# S7G7_footprint_simplified_w_ethernet_v1p.net
KiCad netlist of a schematic drawn in EAGLE
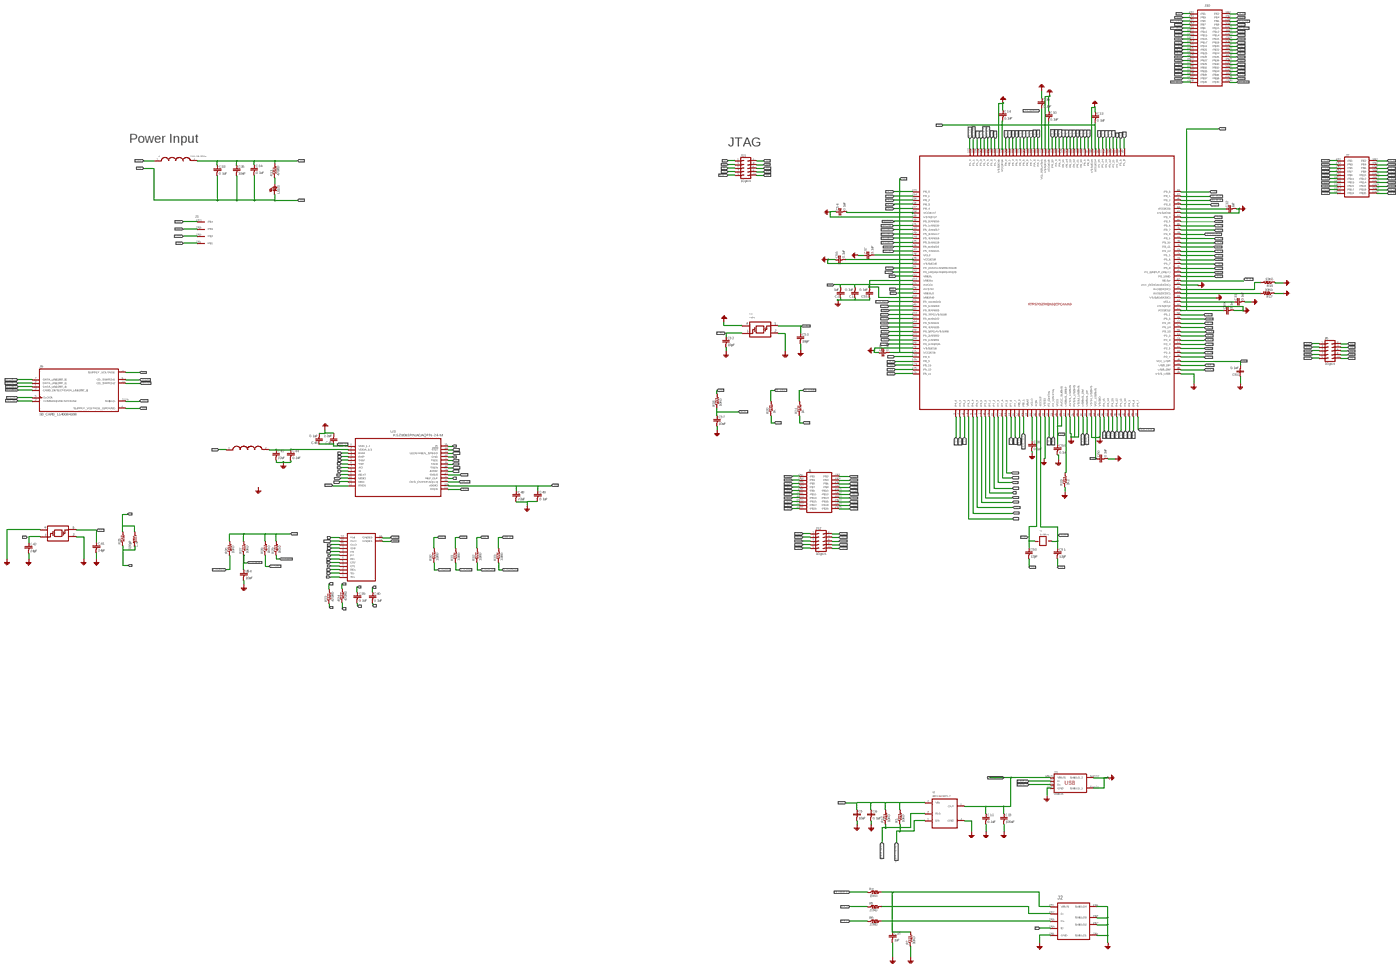
[diagram p0: schematic, sheet 1, overview]
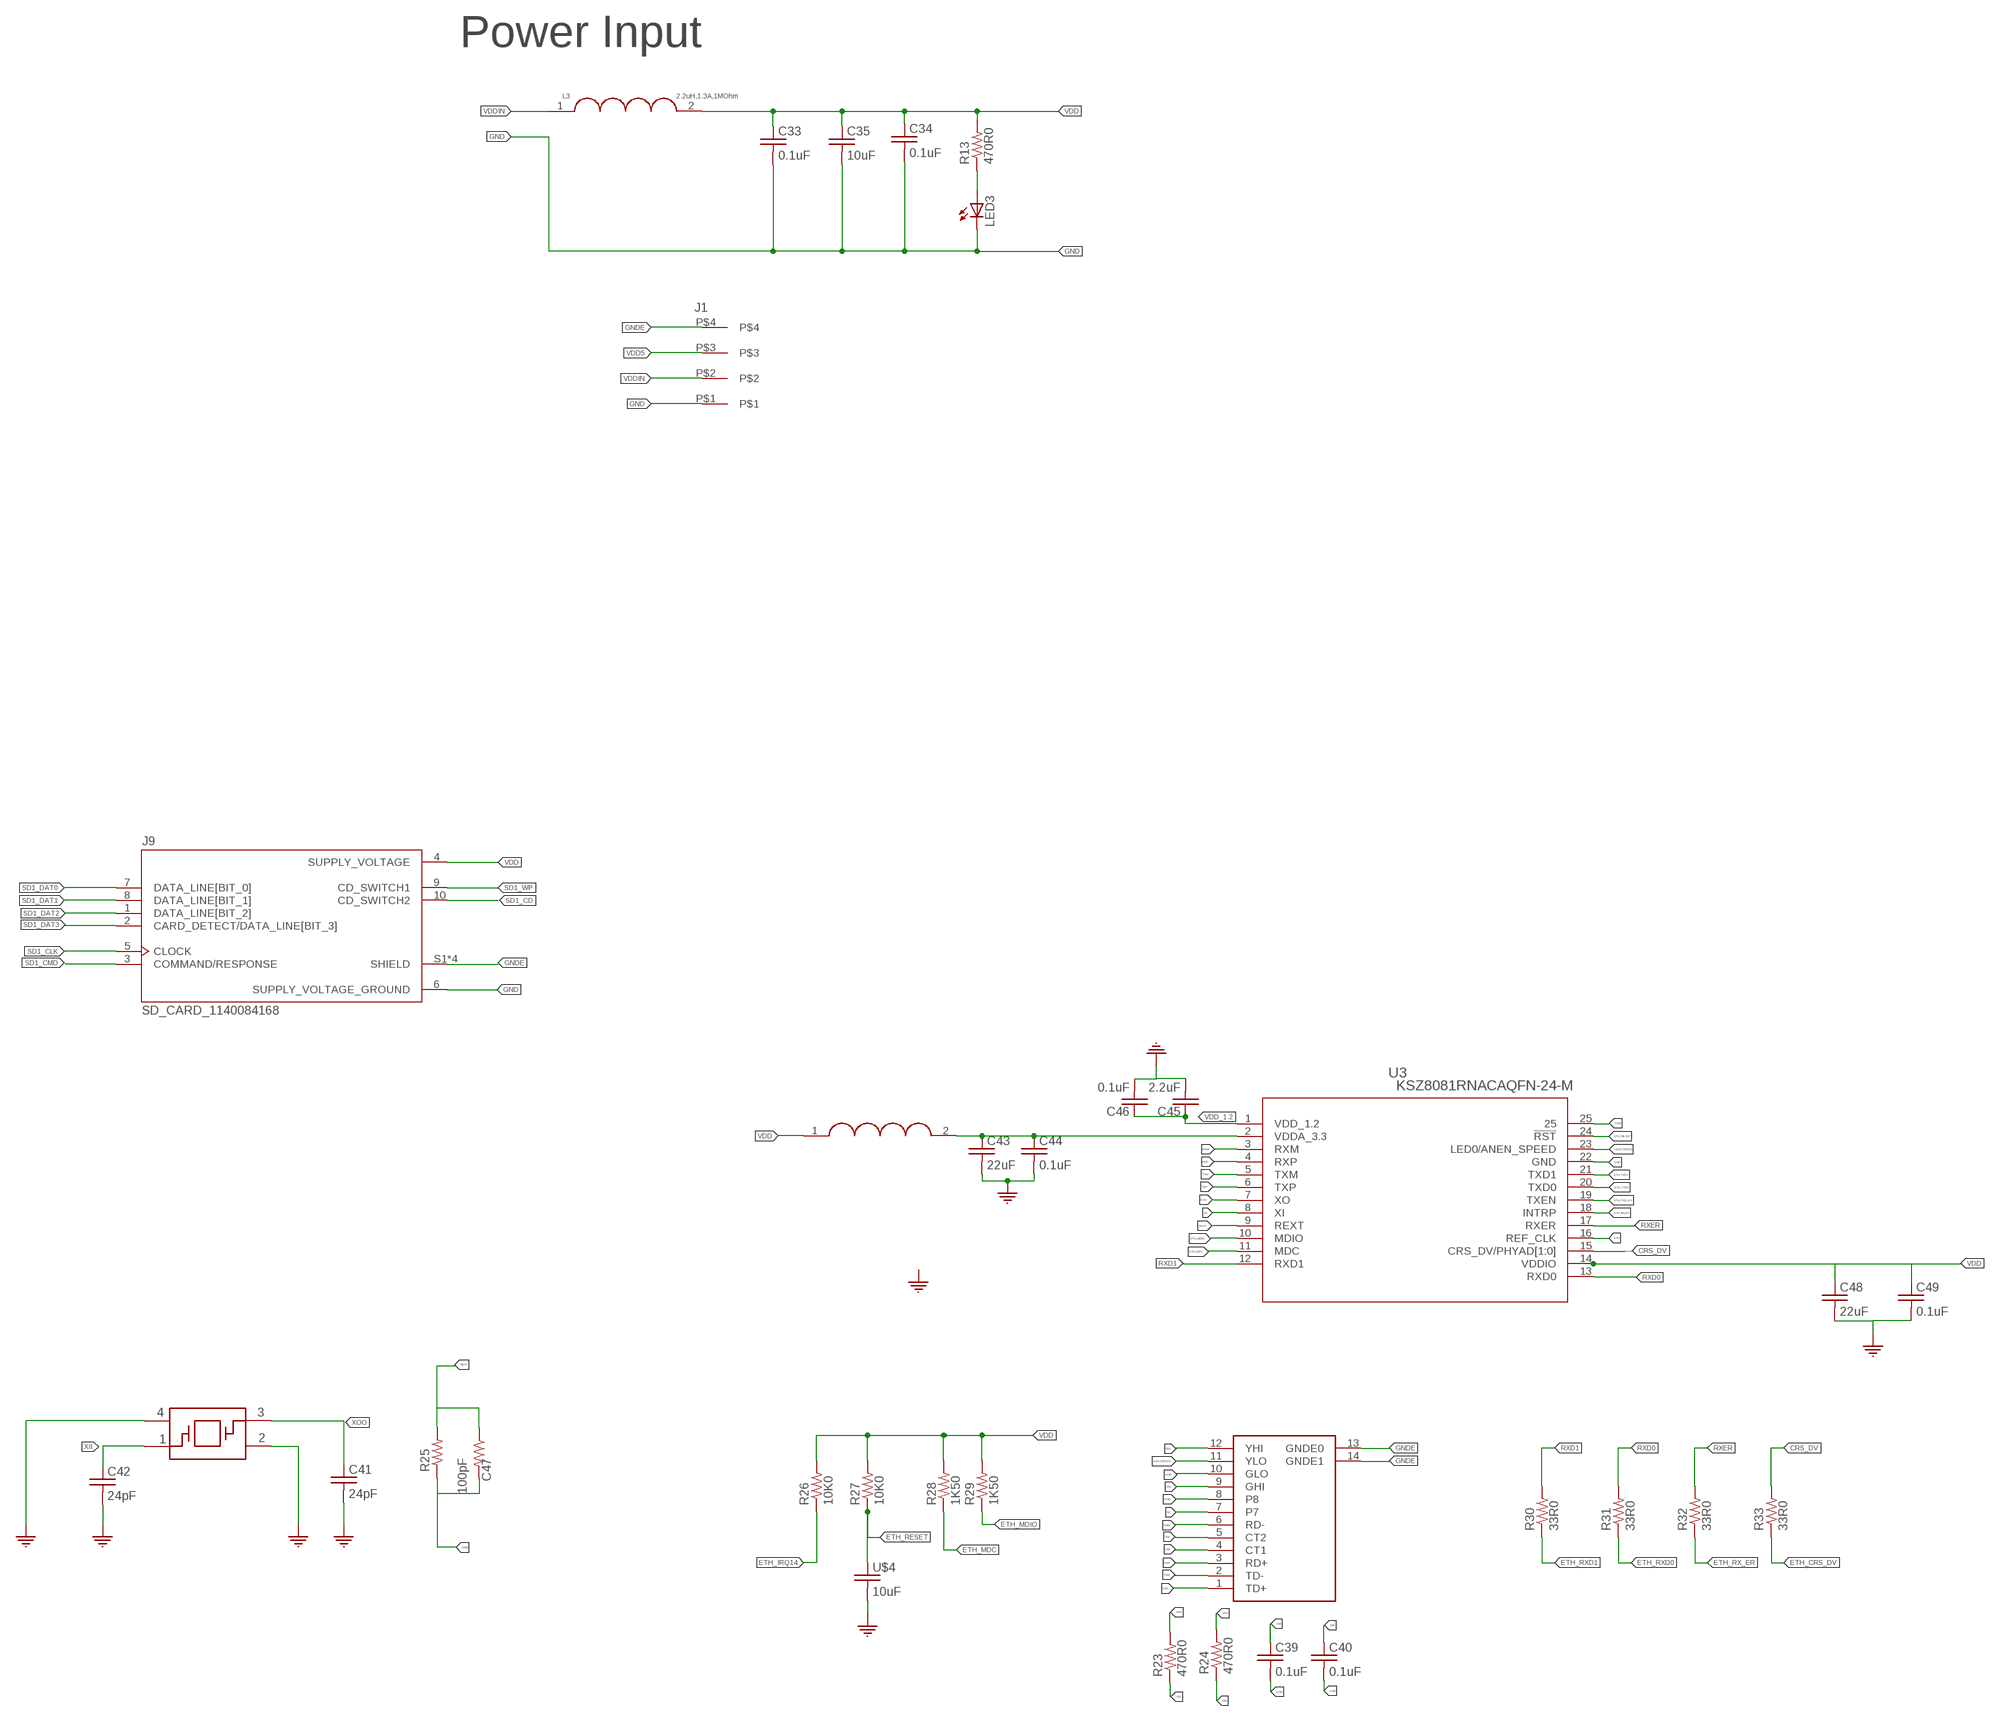
[diagram p1: schematic, sheet 1, part 1 of 4]
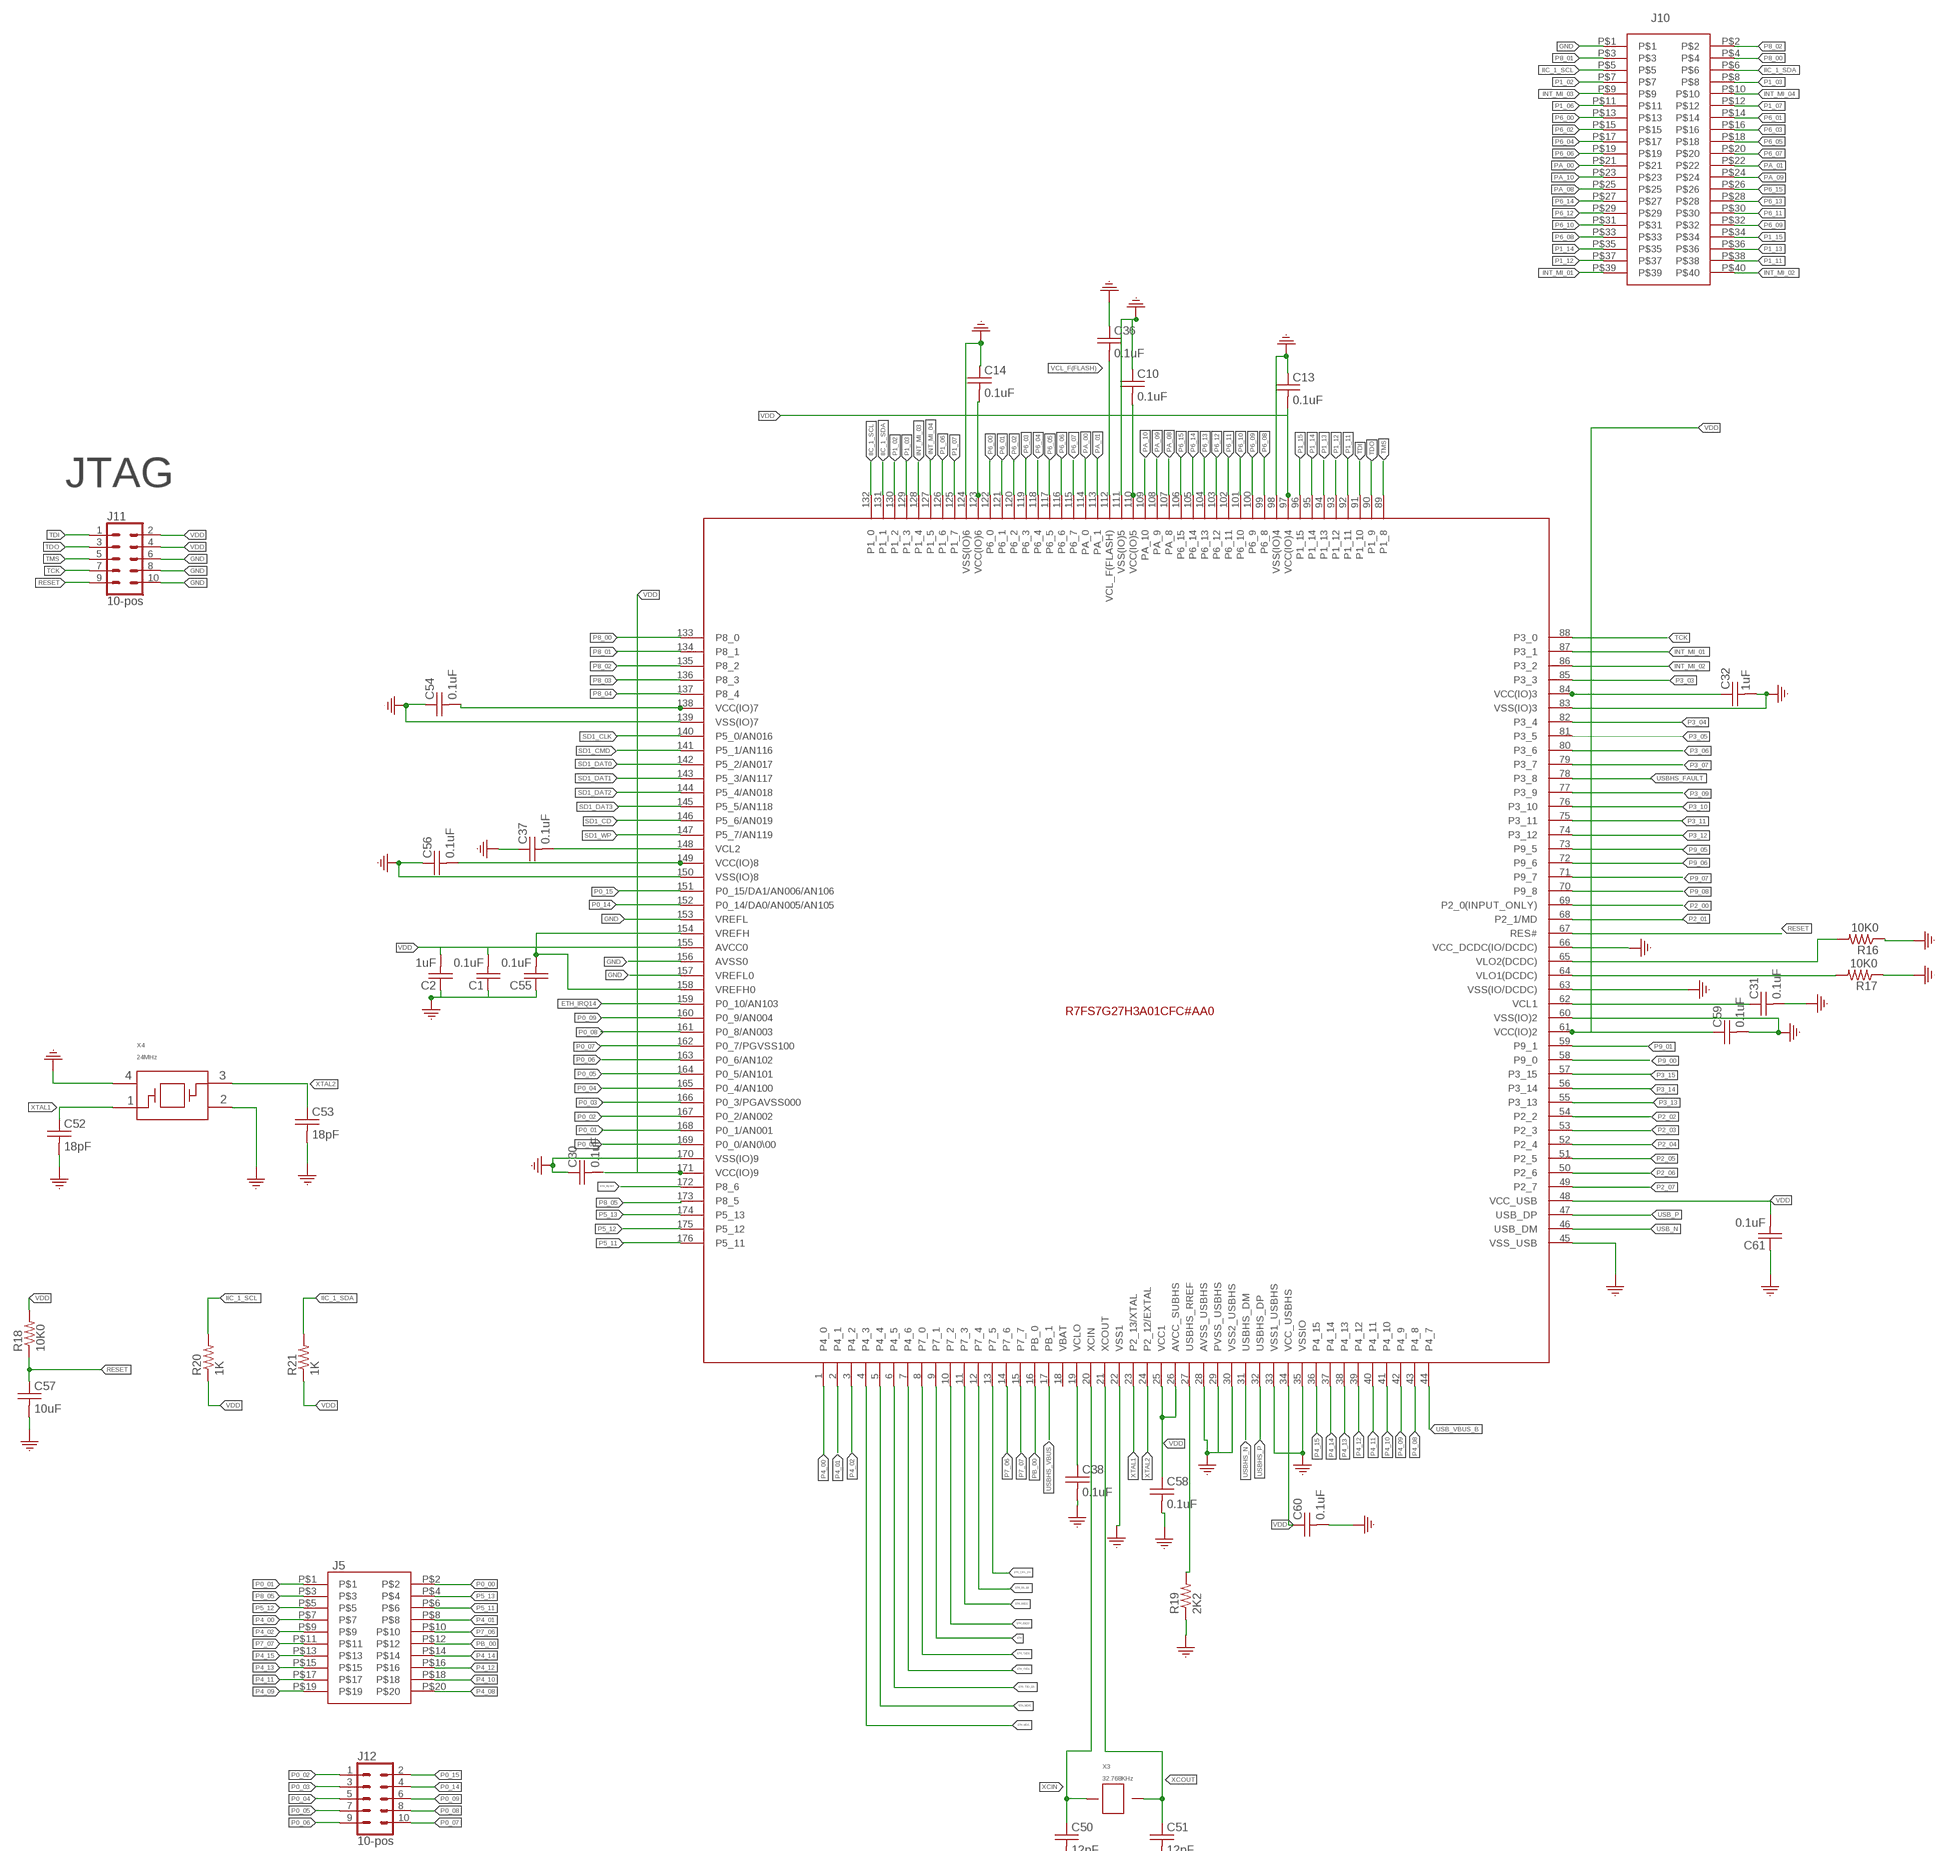
[diagram p2: schematic, sheet 1, part 2 of 4]
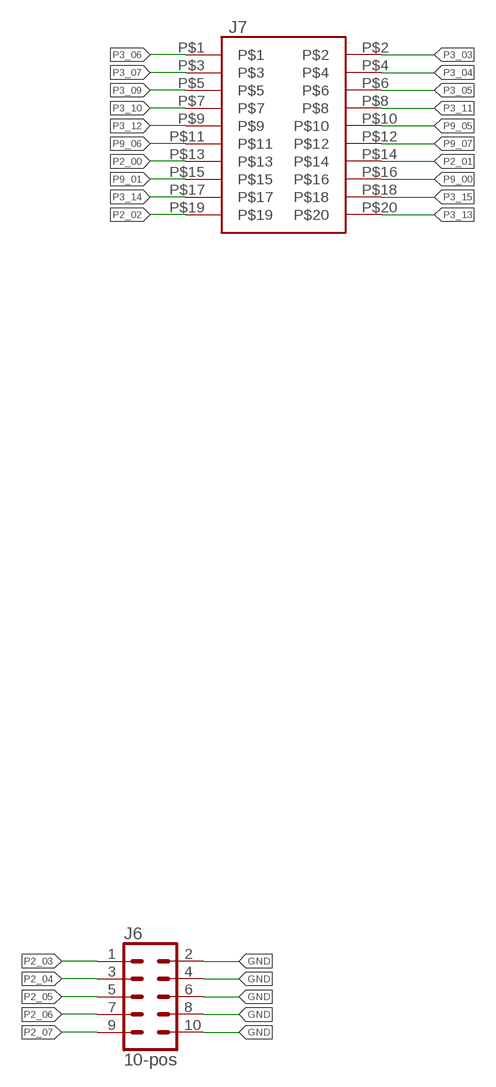
[diagram p3: schematic, sheet 1, part 3 of 4]
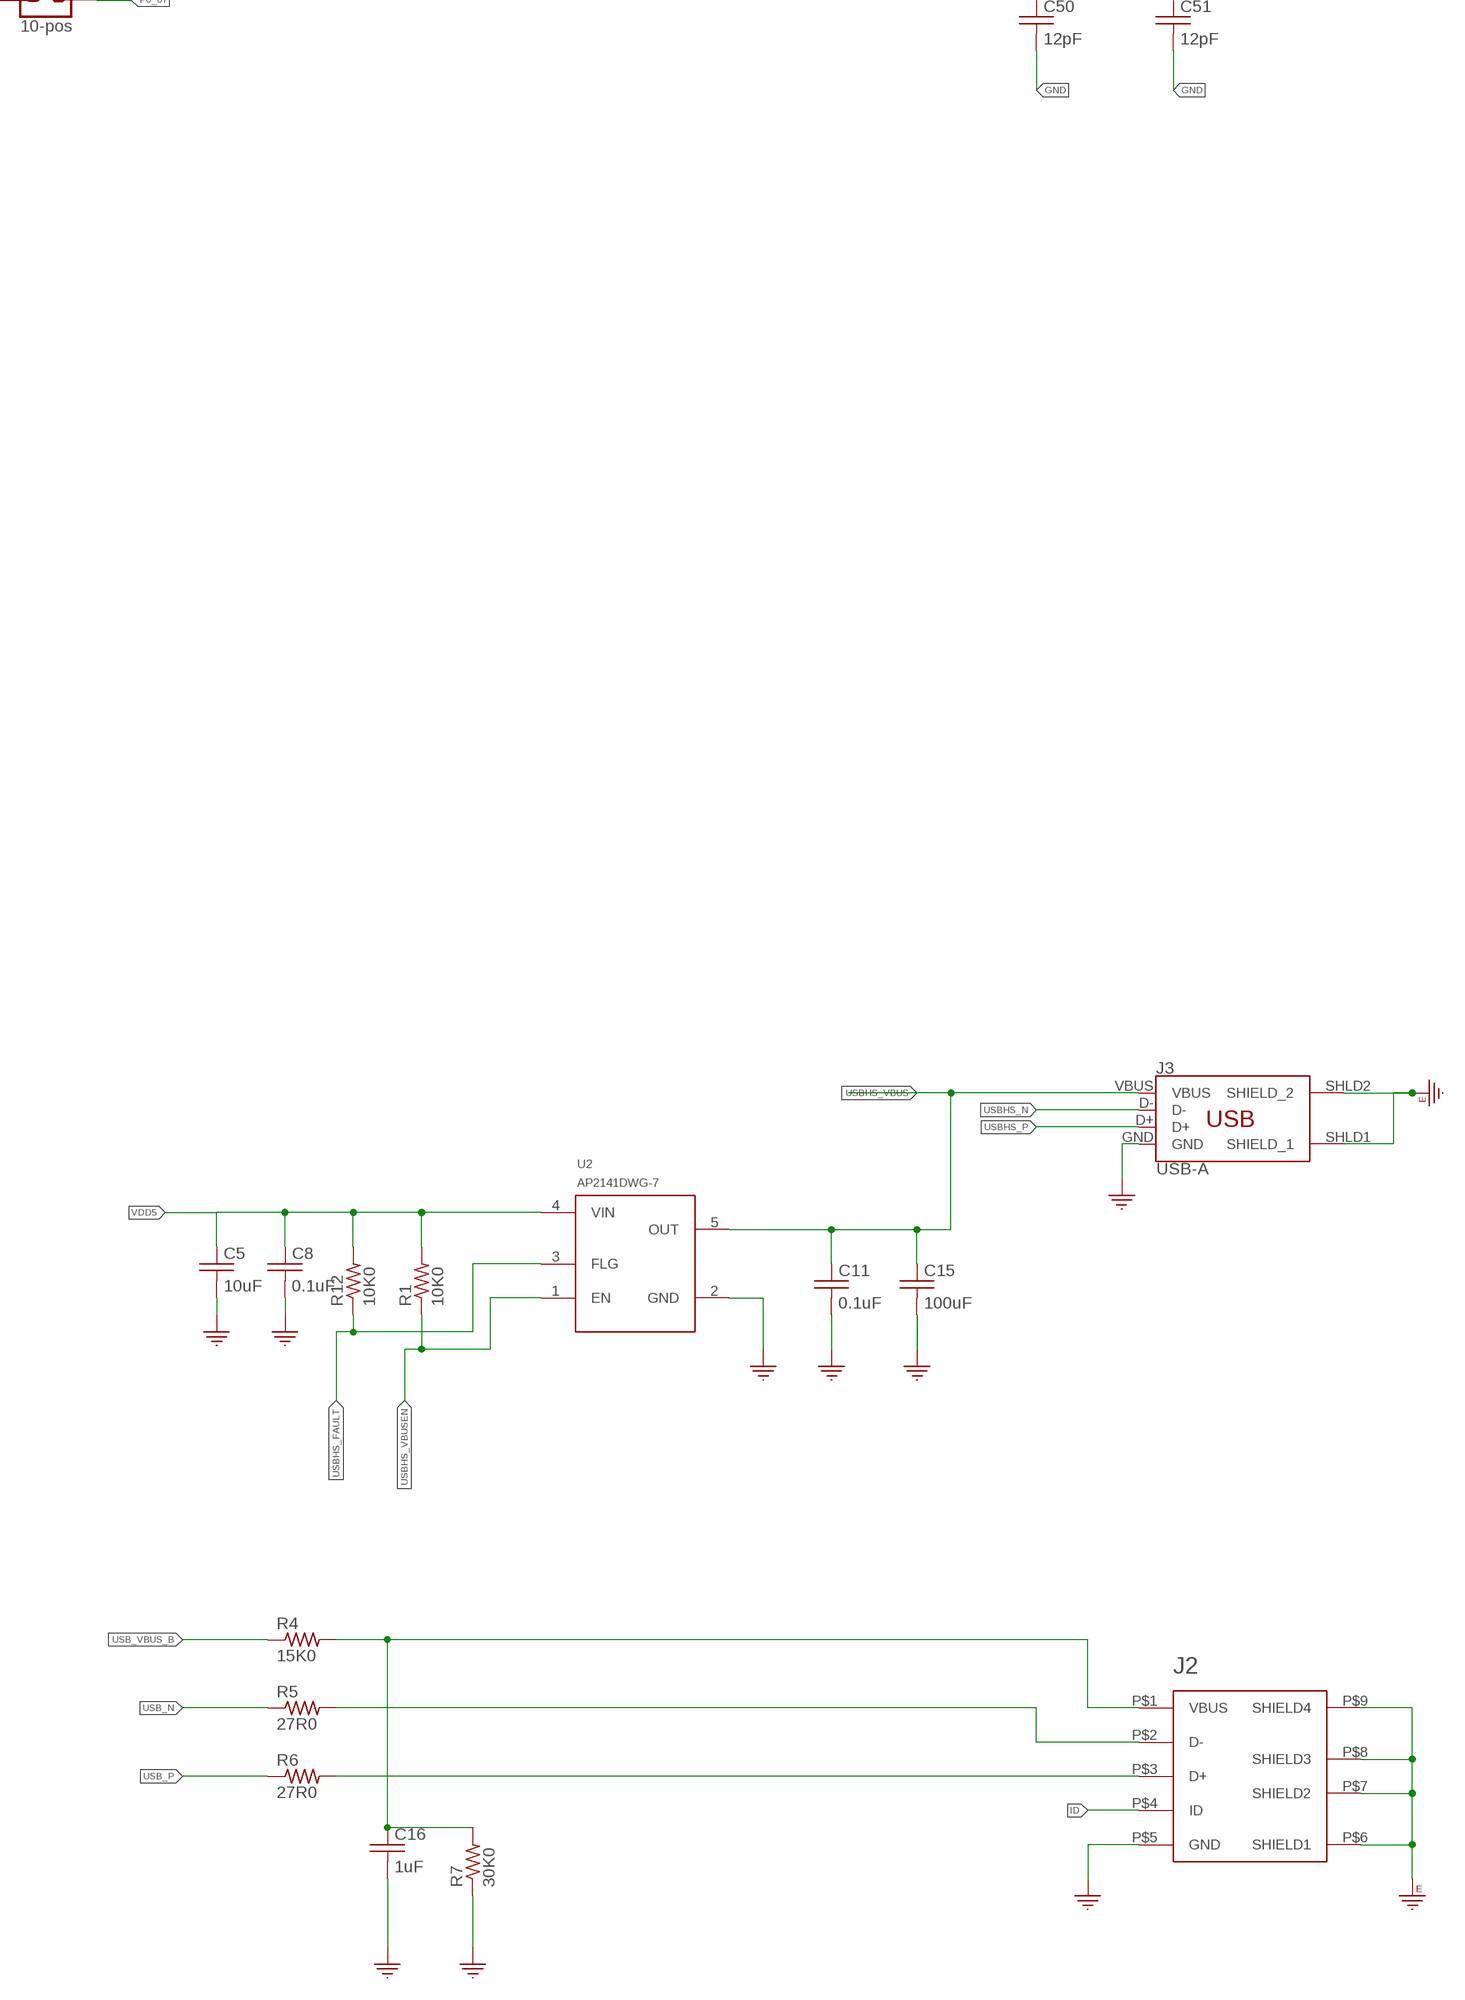
[diagram p4: schematic, sheet 1, part 4 of 4]

(export (version "E")
  (design (tool "Eeschema 10.0.6"))
  (components
    (comp (ref "C1")
      (value "0.1uF")
      (footprint "eagle-import:0402")
      (fields (field (name "PARTNO") "CL05F104ZO5NNNC"))
      (libsource (lib "eagle-import") (part "C_0402_0.1UF"))
    )
    (comp (ref "C2")
      (value "1uF")
      (footprint "eagle-import:0402")
      (fields (field (name "PARTNO") "CL05A105KO5NNNC"))
      (libsource (lib "eagle-import") (part "C_0402_1UF"))
    )
    (comp (ref "C5")
      (value "10uF")
      (footprint "eagle-import:0402")
      (fields (field (name "PARTNO") "CL05A106MP8NUB8"))
      (libsource (lib "eagle-import") (part "C_0402_10UF"))
    )
    (comp (ref "C8")
      (value "0.1uF")
      (footprint "eagle-import:0402")
      (fields (field (name "PARTNO") "CL05F104ZO5NNNC"))
      (libsource (lib "eagle-import") (part "C_0402_0.1UF"))
    )
    (comp (ref "C10")
      (value "0.1uF")
      (footprint "eagle-import:0402")
      (fields (field (name "PARTNO") "CL05F104ZO5NNNC"))
      (libsource (lib "eagle-import") (part "C_0402_0.1UF"))
    )
    (comp (ref "C11")
      (value "0.1uF")
      (footprint "eagle-import:0402")
      (fields (field (name "PARTNO") "CL05F104ZO5NNNC"))
      (libsource (lib "eagle-import") (part "C_0402_0.1UF"))
    )
    (comp (ref "C13")
      (value "0.1uF")
      (footprint "eagle-import:0402")
      (fields (field (name "PARTNO") "CL05F104ZO5NNNC"))
      (libsource (lib "eagle-import") (part "C_0402_0.1UF"))
    )
    (comp (ref "C14")
      (value "0.1uF")
      (footprint "eagle-import:0402")
      (fields (field (name "PARTNO") "CL05F104ZO5NNNC"))
      (libsource (lib "eagle-import") (part "C_0402_0.1UF"))
    )
    (comp (ref "C15")
      (value "100uF")
      (footprint "eagle-import:C1210")
      (fields (field (name "PARTNO") "‎TL8A0107M010D"))
      (libsource (lib "eagle-import") (part "C_1210"))
    )
    (comp (ref "C16")
      (value "1uF")
      (footprint "eagle-import:0402")
      (fields (field (name "PARTNO") "CL05A105KO5NNNC"))
      (libsource (lib "eagle-import") (part "C_0402_1UF"))
    )
    (comp (ref "C30")
      (value "0.1uF")
      (footprint "eagle-import:0402")
      (fields (field (name "PARTNO") "CL05F104ZO5NNNC"))
      (libsource (lib "eagle-import") (part "C_0402_0.1UF"))
    )
    (comp (ref "C31")
      (value "0.1uF")
      (footprint "eagle-import:0402")
      (fields (field (name "PARTNO") "CL05F104ZO5NNNC"))
      (libsource (lib "eagle-import") (part "C_0402_0.1UF"))
    )
    (comp (ref "C32")
      (value "1uF")
      (footprint "eagle-import:0402")
      (fields (field (name "PARTNO") "CL05A105KO5NNNC"))
      (libsource (lib "eagle-import") (part "C_0402_1UF"))
    )
    (comp (ref "C33")
      (value "0.1uF")
      (footprint "eagle-import:0402")
      (fields (field (name "PARTNO") "CL05F104ZO5NNNC"))
      (libsource (lib "eagle-import") (part "C_0402_0.1UF"))
    )
    (comp (ref "C34")
      (value "0.1uF")
      (footprint "eagle-import:0402")
      (fields (field (name "PARTNO") "CL05F104ZO5NNNC"))
      (libsource (lib "eagle-import") (part "C_0402_0.1UF"))
    )
    (comp (ref "C35")
      (value "10uF")
      (footprint "eagle-import:0402")
      (fields (field (name "PARTNO") "CL05A106MP8NUB8"))
      (libsource (lib "eagle-import") (part "C_0402_10UF"))
    )
    (comp (ref "C36")
      (value "0.1uF")
      (footprint "eagle-import:0402")
      (fields (field (name "PARTNO") "CL05F104ZO5NNNC"))
      (libsource (lib "eagle-import") (part "C_0402_0.1UF"))
    )
    (comp (ref "C37")
      (value "0.1uF")
      (footprint "eagle-import:0402")
      (fields (field (name "PARTNO") "CL05F104ZO5NNNC"))
      (libsource (lib "eagle-import") (part "C_0402_0.1UF"))
    )
    (comp (ref "C38")
      (value "0.1uF")
      (footprint "eagle-import:0402")
      (fields (field (name "PARTNO") "CL05F104ZO5NNNC"))
      (libsource (lib "eagle-import") (part "C_0402_0.1UF"))
    )
    (comp (ref "C39")
      (value "0.1uF")
      (footprint "eagle-import:0402")
      (libsource (lib "eagle-import") (part "C_0402"))
    )
    (comp (ref "C40")
      (value "0.1uF")
      (footprint "eagle-import:0402")
      (libsource (lib "eagle-import") (part "C_0402"))
    )
    (comp (ref "C41")
      (value "24pF")
      (footprint "eagle-import:0402")
      (libsource (lib "eagle-import") (part "C_0402"))
    )
    (comp (ref "C42")
      (value "24pF")
      (footprint "eagle-import:0402")
      (libsource (lib "eagle-import") (part "C_0402"))
    )
    (comp (ref "C43")
      (value "22uF")
      (footprint "eagle-import:0603")
      (libsource (lib "eagle-import") (part "C_0603"))
    )
    (comp (ref "C44")
      (value "0.1uF")
      (footprint "eagle-import:0402")
      (libsource (lib "eagle-import") (part "C_0402"))
    )
    (comp (ref "C45")
      (value "2.2uF")
      (footprint "eagle-import:0402")
      (libsource (lib "eagle-import") (part "C_0402"))
    )
    (comp (ref "C46")
      (value "0.1uF")
      (footprint "eagle-import:0402")
      (libsource (lib "eagle-import") (part "C_0402"))
    )
    (comp (ref "C47")
      (value "100pF")
      (footprint "eagle-import:0402")
      (libsource (lib "eagle-import") (part "R_0402"))
    )
    (comp (ref "C48")
      (value "22uF")
      (footprint "eagle-import:0603")
      (libsource (lib "eagle-import") (part "C_0603"))
    )
    (comp (ref "C49")
      (value "0.1uF")
      (footprint "eagle-import:0402")
      (libsource (lib "eagle-import") (part "C_0402"))
    )
    (comp (ref "C50")
      (value "12pF")
      (footprint "eagle-import:0402")
      (fields (field (name "PARTNO") "CL05C120JB5NNNC"))
      (libsource (lib "eagle-import") (part "C_0402_12PF"))
    )
    (comp (ref "C51")
      (value "12pF")
      (footprint "eagle-import:0402")
      (fields (field (name "PARTNO") "CL05C120JB5NNNC"))
      (libsource (lib "eagle-import") (part "C_0402_12PF"))
    )
    (comp (ref "C52")
      (value "18pF")
      (footprint "eagle-import:0402")
      (fields (field (name "PARTNO") "UMK105CG180JV-F"))
      (libsource (lib "eagle-import") (part "C_0402_18PF"))
    )
    (comp (ref "C53")
      (value "18pF")
      (footprint "eagle-import:0402")
      (fields (field (name "PARTNO") "UMK105CG180JV-F"))
      (libsource (lib "eagle-import") (part "C_0402_18PF"))
    )
    (comp (ref "C54")
      (value "0.1uF")
      (footprint "eagle-import:0402")
      (fields (field (name "PARTNO") "CL05F104ZO5NNNC"))
      (libsource (lib "eagle-import") (part "C_0402_0.1UF"))
    )
    (comp (ref "C55")
      (value "0.1uF")
      (footprint "eagle-import:0402")
      (fields (field (name "PARTNO") "CL05F104ZO5NNNC"))
      (libsource (lib "eagle-import") (part "C_0402_0.1UF"))
    )
    (comp (ref "C56")
      (value "0.1uF")
      (footprint "eagle-import:0402")
      (fields (field (name "PARTNO") "CL05F104ZO5NNNC"))
      (libsource (lib "eagle-import") (part "C_0402_0.1UF"))
    )
    (comp (ref "C57")
      (value "10uF")
      (footprint "eagle-import:0402")
      (fields (field (name "PARTNO") "CL05A106MP8NUB8"))
      (libsource (lib "eagle-import") (part "C_0402_10UF"))
    )
    (comp (ref "C58")
      (value "0.1uF")
      (footprint "eagle-import:0402")
      (fields (field (name "PARTNO") "CL05F104ZO5NNNC"))
      (libsource (lib "eagle-import") (part "C_0402_0.1UF"))
    )
    (comp (ref "C59")
      (value "0.1uF")
      (footprint "eagle-import:0402")
      (fields (field (name "PARTNO") "CL05F104ZO5NNNC"))
      (libsource (lib "eagle-import") (part "C_0402_0.1UF"))
    )
    (comp (ref "C60")
      (value "0.1uF")
      (footprint "eagle-import:0402")
      (fields (field (name "PARTNO") "CL05F104ZO5NNNC"))
      (libsource (lib "eagle-import") (part "C_0402_0.1UF"))
    )
    (comp (ref "C61")
      (value "0.1uF")
      (footprint "eagle-import:0402")
      (libsource (lib "eagle-import") (part "C_0402"))
    )
    (comp (ref "FB2/2")
      (value "120Ohm")
      (footprint "eagle-import:0603")
      (libsource (lib "eagle-import") (part "FB_0603_120_OHM0603"))
    )
    (comp (ref "J1")
      (value "4-pos")
      (footprint "eagle-import:1X4_3.81MM_PITCH")
      (fields (field (name "PARTNO") "691322310004"))
      (libsource (lib "eagle-import") (part "3.81MM_1_X_4_RT_ANGLE_PLUG_HEADER"))
    )
    (comp (ref "J2")
      (value "USB-B-Micro")
      (footprint "eagle-import:USB_MICRO-B")
      (fields (field (name "PARTNO") "10118192-0002LF"))
      (libsource (lib "eagle-import") (part "USB_MICRO-B"))
    )
    (comp (ref "J3")
      (value "USB-A")
      (footprint "eagle-import:USB_A_SMT")
      (fields (field (name "PARTNO") "87583-3010RPALF"))
      (libsource (lib "eagle-import") (part "USB_A"))
    )
    (comp (ref "J4")
      (value "RJ45_WITH_ELEC")
      (footprint "eagle-import:RJ45_TH_ELEC")
      (libsource (lib "eagle-import") (part "RJ45_WITH_ELEC"))
    )
    (comp (ref "J5")
      (value "2_X_10_HEADER_GENERIC")
      (footprint "eagle-import:2_X_10_.1_INCH")
      (libsource (lib "eagle-import") (part "2_X_10_HEADER_GENERIC"))
    )
    (comp (ref "J6")
      (value "10-pos")
      (footprint "eagle-import:2X5")
      (fields (field (name "PARTNO") "PH2RA-10-UA"))
      (libsource (lib "eagle-import") (part "CONN_05X2_RAPTH"))
    )
    (comp (ref "J7")
      (value "2_X_10_HEADER_GENERIC")
      (footprint "eagle-import:2_X_10_.1_INCH")
      (libsource (lib "eagle-import") (part "2_X_10_HEADER_GENERIC"))
    )
    (comp (ref "J9")
      (value "SD_CARD_1140084168")
      (footprint "eagle-import:AMPHENOL_1140084168")
      (fields (field (name "MF") "Amphenol ICC") (field (name "PARTNO") "114-00841-68"))
      (libsource (lib "eagle-import") (part "SD_CARD_1140084168"))
    )
    (comp (ref "J10")
      (value "40-pos")
      (footprint "eagle-import:HEADER_2_X_20_.1_INCH")
      (fields (field (name "PARTNO") "61304021021"))
      (libsource (lib "eagle-import") (part "HEADER_2_X_20_GENERIC"))
    )
    (comp (ref "J11")
      (value "10-pos")
      (footprint "eagle-import:2X5")
      (fields (field (name "PARTNO") "PH2RA-10-UA"))
      (libsource (lib "eagle-import") (part "CONN_05X2_RAPTH"))
    )
    (comp (ref "J12")
      (value "10-pos")
      (footprint "eagle-import:2X5")
      (fields (field (name "PARTNO") "PH2RA-10-UA"))
      (libsource (lib "eagle-import") (part "CONN_05X2_RAPTH"))
    )
    (comp (ref "L3")
      (value "2.2uH,1.3A,1MOhm")
      (footprint "eagle-import:1008_(2520_METRIC)")
      (fields (field (name "PARTNO") "LQM2HPN2R2MG0L"))
      (libsource (lib "eagle-import") (part "INDUCTOR_1008_2.2_MH_1.3A"))
    )
    (comp (ref "LED3")
      (value "Green")
      (footprint "eagle-import:LED_0805_GREEN")
      (fields (field (name "PARTNO") "LG R971-KN-1"))
      (libsource (lib "eagle-import") (part "LED_0805_GREEN"))
    )
    (comp (ref "R1")
      (value "10K0")
      (footprint "eagle-import:0402")
      (fields (field (name "PARTNO") "RMCF0402JT10K0"))
      (libsource (lib "eagle-import") (part "R_0402_10K0"))
    )
    (comp (ref "R4")
      (value "15K0")
      (footprint "eagle-import:0402")
      (fields (field (name "PARTNO") "RMCF0402JT15K0"))
      (libsource (lib "eagle-import") (part "R_0402_15K0"))
    )
    (comp (ref "R5")
      (value "27R0")
      (footprint "eagle-import:0402")
      (fields (field (name "PARTNO") "RMCF0402JT27R0"))
      (libsource (lib "eagle-import") (part "R_0402_27R0"))
    )
    (comp (ref "R6")
      (value "27R0")
      (footprint "eagle-import:0402")
      (fields (field (name "PARTNO") "RMCF0402JT27R0"))
      (libsource (lib "eagle-import") (part "R_0402_27R0"))
    )
    (comp (ref "R7")
      (value "30K0")
      (footprint "eagle-import:0402")
      (fields (field (name "PARTNO") "RC0402JR-0730KL"))
      (libsource (lib "eagle-import") (part "R_0402_30K0"))
    )
    (comp (ref "R12")
      (value "10K0")
      (footprint "eagle-import:0402")
      (fields (field (name "PARTNO") "RMCF0402JT10K0"))
      (libsource (lib "eagle-import") (part "R_0402_10K0"))
    )
    (comp (ref "R13")
      (value "470R0")
      (footprint "eagle-import:0402")
      (fields (field (name "PARTNO") "RMCF0402JT470R"))
      (libsource (lib "eagle-import") (part "R_0402_470R0"))
    )
    (comp (ref "R16")
      (value "10K0")
      (footprint "eagle-import:0402")
      (fields (field (name "PARTNO") "RMCF0402JT10K0"))
      (libsource (lib "eagle-import") (part "R_0402_10K0"))
    )
    (comp (ref "R17")
      (value "10K0")
      (footprint "eagle-import:0402")
      (fields (field (name "PARTNO") "RMCF0402JT10K0"))
      (libsource (lib "eagle-import") (part "R_0402_10K0"))
    )
    (comp (ref "R18")
      (value "10K0")
      (footprint "eagle-import:0402")
      (fields (field (name "PARTNO") "RMCF0402JT10K0"))
      (libsource (lib "eagle-import") (part "R_0402_10K0"))
    )
    (comp (ref "R19")
      (value "2K2")
      (footprint "eagle-import:0402")
      (fields (field (name "PARTNO") "RMCF0402JT2K20"))
      (libsource (lib "eagle-import") (part "R_0402_2K2"))
    )
    (comp (ref "R20")
      (value "1K")
      (footprint "eagle-import:0402")
      (libsource (lib "eagle-import") (part "R_0402"))
    )
    (comp (ref "R21")
      (value "1K")
      (footprint "eagle-import:0402")
      (libsource (lib "eagle-import") (part "R_0402"))
    )
    (comp (ref "R23")
      (value "470R0")
      (footprint "eagle-import:0402")
      (libsource (lib "eagle-import") (part "R_0402"))
    )
    (comp (ref "R24")
      (value "470R0")
      (footprint "eagle-import:0402")
      (libsource (lib "eagle-import") (part "R_0402"))
    )
    (comp (ref "R25")
      (value "6k49")
      (footprint "eagle-import:0402")
      (libsource (lib "eagle-import") (part "R_0402"))
    )
    (comp (ref "R26")
      (value "10K0")
      (footprint "eagle-import:0402")
      (libsource (lib "eagle-import") (part "R_0402"))
    )
    (comp (ref "R27")
      (value "10K0")
      (footprint "eagle-import:0402")
      (libsource (lib "eagle-import") (part "R_0402"))
    )
    (comp (ref "R28")
      (value "1K50")
      (footprint "eagle-import:0402")
      (libsource (lib "eagle-import") (part "R_0402"))
    )
    (comp (ref "R29")
      (value "1K50")
      (footprint "eagle-import:0402")
      (libsource (lib "eagle-import") (part "R_0402"))
    )
    (comp (ref "R30")
      (value "33R0")
      (footprint "eagle-import:0402")
      (libsource (lib "eagle-import") (part "R_0402"))
    )
    (comp (ref "R31")
      (value "33R0")
      (footprint "eagle-import:0402")
      (libsource (lib "eagle-import") (part "R_0402"))
    )
    (comp (ref "R32")
      (value "33R0")
      (footprint "eagle-import:0402")
      (libsource (lib "eagle-import") (part "R_0402"))
    )
    (comp (ref "R33")
      (value "33R0")
      (footprint "eagle-import:0402")
      (libsource (lib "eagle-import") (part "R_0402"))
    )
    (comp (ref "U$3")
      (value "25MHz")
      (footprint "eagle-import:SMD_3225")
      (fields (field (name "PARTNO") "FA-238 25.0000MB-B3"))
      (libsource (lib "eagle-import") (part "XTAL_25_MHZ"))
    )
    (comp (ref "U$4")
      (value "10uF")
      (footprint "eagle-import:0402")
      (libsource (lib "eagle-import") (part "C_0402"))
    )
    (comp (ref "U2")
      (value "AP2151DWG-7")
      (footprint "eagle-import:SOT-23-5")
      (fields (field (name "PARTNO") "AP2151WG-7"))
      (libsource (lib "eagle-import") (part "AP2151DWG-7"))
    )
    (comp (ref "U3")
      (value "KSZ8081RNACAQFN-24-M")
      (footprint "eagle-import:QFN-24-M")
      (fields (field (name "MANUFACTURER_PART_NUMBER") "KSZ8081RNACA"))
      (libsource (lib "eagle-import") (part "KSZ8081RNACAQFN-24-M"))
    )
    (comp (ref "U4")
      (value "S7G2LQFP176")
      (footprint "eagle-import:LQFP176_24X24")
      (fields (field (name "PARTNO") "R7FS7G27H3A01CFC#AA0"))
      (libsource (lib "eagle-import") (part "S7G2_X_176"))
    )
    (comp (ref "X3")
      (value "32.768KHz")
      (footprint "eagle-import:SMD_X_2_PADS")
      (fields (field (name "PARTNO") "ABS07-32.768KHZ-T"))
      (libsource (lib "eagle-import") (part "XTAL_32.768KHZ"))
    )
    (comp (ref "X4")
      (value "24MHz")
      (footprint "eagle-import:SMD_3225")
      (fields (field (name "PARTNO") "FA-238 24.0000MB-C3 "))
      (libsource (lib "eagle-import") (part "XTAL_24_MHZ"))
    )
  )
  (nets
    (net (code "1") (name "C58") (class "Default")
      (node (ref "C39") (pin "P$1") (pinfunction "1_P$1") (pintype "passive"))
      (node (ref "J4") (pin "4") (pinfunction "CT1_4") (pintype "bidirectional"))
    )
    (net (code "2") (name "C60") (class "Default")
      (node (ref "C40") (pin "P$1") (pinfunction "1_P$1") (pintype "passive"))
      (node (ref "J4") (pin "5") (pinfunction "CT2_5") (pintype "bidirectional"))
    )
    (net (code "3") (name "CRS_DV") (class "Default")
      (node (ref "R33") (pin "P$2") (pinfunction "2_P$2") (pintype "passive"))
      (node (ref "U3") (pin "15") (pinfunction "CRS_DV/PHYAD[1:0]_15") (pintype "bidirectional"))
    )
    (net (code "4") (name "ETH") (class "Default")
      (node (ref "U3") (pin "16") (pinfunction "REF_CLK_16") (pintype "bidirectional"))
      (node (ref "U4") (pin "9") (pinfunction "P7_1_9") (pintype "bidirectional"))
    )
    (net (code "5") (name "ETH_CRS_DV") (class "Default")
      (node (ref "R33") (pin "P$1") (pinfunction "1_P$1") (pintype "passive"))
      (node (ref "U4") (pin "13") (pinfunction "P7_5_13") (pintype "bidirectional"))
    )
    (net (code "6") (name "ETH_IRQ14") (class "Default")
      (node (ref "R26") (pin "P$1") (pinfunction "1_P$1") (pintype "passive"))
      (node (ref "U3") (pin "18") (pinfunction "INTRP_18") (pintype "bidirectional"))
      (node (ref "U4") (pin "159") (pinfunction "P0_10/AN103_159") (pintype "bidirectional"))
    )
    (net (code "7") (name "ETH_MDC") (class "Default")
      (node (ref "R28") (pin "P$1") (pinfunction "1_P$1") (pintype "passive"))
      (node (ref "U3") (pin "11") (pinfunction "MDC_11") (pintype "input"))
      (node (ref "U4") (pin "4") (pinfunction "P4_3_4") (pintype "bidirectional"))
    )
    (net (code "8") (name "ETH_MDIO") (class "Default")
      (node (ref "R29") (pin "P$1") (pinfunction "1_P$1") (pintype "passive"))
      (node (ref "U3") (pin "10") (pinfunction "MDIO_10") (pintype "bidirectional"))
      (node (ref "U4") (pin "5") (pinfunction "P4_4_5") (pintype "bidirectional"))
    )
    (net (code "9") (name "ETH_RESET") (class "Default")
      (node (ref "R27") (pin "P$1") (pinfunction "1_P$1") (pintype "passive"))
      (node (ref "U$4") (pin "P$1") (pinfunction "1_P$1") (pintype "passive"))
      (node (ref "U3") (pin "24") (pinfunction "~{RST}_24") (pintype "input"))
      (node (ref "U4") (pin "172") (pinfunction "P8_6_172") (pintype "bidirectional"))
    )
    (net (code "10") (name "ETH_RXD0") (class "Default")
      (node (ref "R31") (pin "P$1") (pinfunction "1_P$1") (pintype "passive"))
      (node (ref "U4") (pin "10") (pinfunction "P7_2_10") (pintype "bidirectional"))
    )
    (net (code "11") (name "ETH_RXD1") (class "Default")
      (node (ref "R30") (pin "P$1") (pinfunction "1_P$1") (pintype "passive"))
      (node (ref "U4") (pin "11") (pinfunction "P7_3_11") (pintype "bidirectional"))
    )
    (net (code "12") (name "ETH_RX_ER") (class "Default")
      (node (ref "R32") (pin "P$1") (pinfunction "1_P$1") (pintype "passive"))
      (node (ref "U4") (pin "12") (pinfunction "P7_4_12") (pintype "bidirectional"))
    )
    (net (code "13") (name "ETH_TXD0") (class "Default")
      (node (ref "U3") (pin "20") (pinfunction "TXD0_20") (pintype "input"))
      (node (ref "U4") (pin "8") (pinfunction "P7_0_8") (pintype "bidirectional"))
    )
    (net (code "14") (name "ETH_TXD1") (class "Default")
      (node (ref "U3") (pin "21") (pinfunction "TXD1_21") (pintype "bidirectional"))
      (node (ref "U4") (pin "7") (pinfunction "P4_6_7") (pintype "bidirectional"))
    )
    (net (code "15") (name "ETH_TXD_EN") (class "Default")
      (node (ref "U3") (pin "19") (pinfunction "TXEN_19") (pintype "input"))
      (node (ref "U4") (pin "6") (pinfunction "P4_5_6") (pintype "bidirectional"))
    )
    (net (code "16") (name "GND") (class "Default")
      (node (ref "C1") (pin "P$1") (pinfunction "1_P$1") (pintype "passive"))
      (node (ref "C10") (pin "P$1") (pinfunction "1_P$1") (pintype "passive"))
      (node (ref "C11") (pin "P$2") (pinfunction "2_P$2") (pintype "passive"))
      (node (ref "C13") (pin "P$1") (pinfunction "1_P$1") (pintype "passive"))
      (node (ref "C14") (pin "P$1") (pinfunction "1_P$1") (pintype "passive"))
      (node (ref "C15") (pin "2") (pinfunction "2_2") (pintype "passive"))
      (node (ref "C16") (pin "P$2") (pinfunction "2_P$2") (pintype "passive"))
      (node (ref "C2") (pin "P$1") (pinfunction "1_P$1") (pintype "passive"))
      (node (ref "C30") (pin "P$1") (pinfunction "1_P$1") (pintype "passive"))
      (node (ref "C31") (pin "P$2") (pinfunction "2_P$2") (pintype "passive"))
      (node (ref "C32") (pin "P$2") (pinfunction "2_P$2") (pintype "passive"))
      (node (ref "C33") (pin "P$2") (pinfunction "2_P$2") (pintype "passive"))
      (node (ref "C34") (pin "P$2") (pinfunction "2_P$2") (pintype "passive"))
      (node (ref "C35") (pin "P$2") (pinfunction "2_P$2") (pintype "passive"))
      (node (ref "C36") (pin "P$1") (pinfunction "1_P$1") (pintype "passive"))
      (node (ref "C37") (pin "P$1") (pinfunction "1_P$1") (pintype "passive"))
      (node (ref "C38") (pin "P$2") (pinfunction "2_P$2") (pintype "passive"))
      (node (ref "C39") (pin "P$2") (pinfunction "2_P$2") (pintype "passive"))
      (node (ref "C40") (pin "P$2") (pinfunction "2_P$2") (pintype "passive"))
      (node (ref "C41") (pin "P$2") (pinfunction "2_P$2") (pintype "passive"))
      (node (ref "C42") (pin "P$2") (pinfunction "2_P$2") (pintype "passive"))
      (node (ref "C43") (pin "2") (pinfunction "2_2") (pintype "passive"))
      (node (ref "C44") (pin "P$2") (pinfunction "2_P$2") (pintype "passive"))
      (node (ref "C45") (pin "P$2") (pinfunction "2_P$2") (pintype "passive"))
      (node (ref "C46") (pin "P$2") (pinfunction "2_P$2") (pintype "passive"))
      (node (ref "C47") (pin "P$2") (pinfunction "2_P$2") (pintype "passive"))
      (node (ref "C48") (pin "2") (pinfunction "2_2") (pintype "passive"))
      (node (ref "C49") (pin "P$2") (pinfunction "2_P$2") (pintype "passive"))
      (node (ref "C5") (pin "P$2") (pinfunction "2_P$2") (pintype "passive"))
      (node (ref "C50") (pin "P$2") (pinfunction "2_P$2") (pintype "passive"))
      (node (ref "C51") (pin "P$2") (pinfunction "2_P$2") (pintype "passive"))
      (node (ref "C52") (pin "P$2") (pinfunction "2_P$2") (pintype "passive"))
      (node (ref "C53") (pin "P$2") (pinfunction "2_P$2") (pintype "passive"))
      (node (ref "C54") (pin "P$1") (pinfunction "1_P$1") (pintype "passive"))
      (node (ref "C55") (pin "P$1") (pinfunction "1_P$1") (pintype "passive"))
      (node (ref "C56") (pin "P$1") (pinfunction "1_P$1") (pintype "passive"))
      (node (ref "C57") (pin "P$2") (pinfunction "2_P$2") (pintype "passive"))
      (node (ref "C58") (pin "P$2") (pinfunction "2_P$2") (pintype "passive"))
      (node (ref "C59") (pin "P$2") (pinfunction "2_P$2") (pintype "passive"))
      (node (ref "C60") (pin "P$2") (pinfunction "2_P$2") (pintype "passive"))
      (node (ref "C61") (pin "P$1") (pinfunction "1_P$1") (pintype "passive"))
      (node (ref "C8") (pin "P$2") (pinfunction "2_P$2") (pintype "passive"))
      (node (ref "J1") (pin "P$1") (pinfunction "P$1_P$1") (pintype "bidirectional"))
      (node (ref "J10") (pin "P$1") (pinfunction "P$1_P$1") (pintype "bidirectional"))
      (node (ref "J11") (pin "10") (pinfunction "10_10") (pintype "passive"))
      (node (ref "J11") (pin "6") (pinfunction "6_6") (pintype "passive"))
      (node (ref "J11") (pin "8") (pinfunction "8_8") (pintype "passive"))
      (node (ref "J2") (pin "P$5") (pinfunction "GND_P$5") (pintype "bidirectional"))
      (node (ref "J3") (pin "GND") (pinfunction "GND_GND") (pintype "power_in"))
      (node (ref "J4") (pin "10") (pinfunction "GLO_10") (pintype "bidirectional"))
      (node (ref "J4") (pin "8") (pinfunction "P8_8") (pintype "bidirectional"))
      (node (ref "J6") (pin "10") (pinfunction "10_10") (pintype "passive"))
      (node (ref "J6") (pin "2") (pinfunction "2_2") (pintype "passive"))
      (node (ref "J6") (pin "4") (pinfunction "4_4") (pintype "passive"))
      (node (ref "J6") (pin "6") (pinfunction "6_6") (pintype "passive"))
      (node (ref "J6") (pin "8") (pinfunction "8_8") (pintype "passive"))
      (node (ref "J9") (pin "6") (pinfunction "SUPPLY_VOLTAGE_GROUND_6") (pintype "power_in"))
      (node (ref "LED3") (pin "C") (pinfunction "C_C") (pintype "passive"))
      (node (ref "R16") (pin "P$1") (pinfunction "1_P$1") (pintype "passive"))
      (node (ref "R17") (pin "P$1") (pinfunction "1_P$1") (pintype "passive"))
      (node (ref "R19") (pin "P$1") (pinfunction "1_P$1") (pintype "passive"))
      (node (ref "R25") (pin "P$1") (pinfunction "1_P$1") (pintype "passive"))
      (node (ref "R7") (pin "P$1") (pinfunction "1_P$1") (pintype "passive"))
      (node (ref "U$3") (pin "2") (pinfunction "2_2") (pintype "bidirectional"))
      (node (ref "U$3") (pin "4") (pinfunction "4_4") (pintype "bidirectional"))
      (node (ref "U$4") (pin "P$2") (pinfunction "2_P$2") (pintype "passive"))
      (node (ref "U2") (pin "2") (pinfunction "GND_2") (pintype "input"))
      (node (ref "U3") (pin "22") (pinfunction "GND_22") (pintype "power_in"))
      (node (ref "U3") (pin "25") (pinfunction "25_25") (pintype "passive"))
      (node (ref "U4") (pin "111") (pinfunction "VSS(IO)5_111") (pintype "bidirectional"))
      (node (ref "U4") (pin "124") (pinfunction "VSS(IO)6_124") (pintype "bidirectional"))
      (node (ref "U4") (pin "139") (pinfunction "VSS(IO)7_139") (pintype "bidirectional"))
      (node (ref "U4") (pin "150") (pinfunction "VSS(IO)8_150") (pintype "bidirectional"))
      (node (ref "U4") (pin "153") (pinfunction "VREFL_153") (pintype "bidirectional"))
      (node (ref "U4") (pin "156") (pinfunction "AVSS0_156") (pintype "bidirectional"))
      (node (ref "U4") (pin "157") (pinfunction "VREFL0_157") (pintype "bidirectional"))
      (node (ref "U4") (pin "170") (pinfunction "VSS(IO)9_170") (pintype "bidirectional"))
      (node (ref "U4") (pin "22") (pinfunction "VSS1_22") (pintype "bidirectional"))
      (node (ref "U4") (pin "28") (pinfunction "AVSS_USBHS_28") (pintype "bidirectional"))
      (node (ref "U4") (pin "29") (pinfunction "PVSS_USBHS_29") (pintype "bidirectional"))
      (node (ref "U4") (pin "30") (pinfunction "VSS2_USBHS_30") (pintype "bidirectional"))
      (node (ref "U4") (pin "33") (pinfunction "VSS1_USBHS_33") (pintype "bidirectional"))
      (node (ref "U4") (pin "35") (pinfunction "VSSIO_35") (pintype "bidirectional"))
      (node (ref "U4") (pin "45") (pinfunction "VSS_USB_45") (pintype "bidirectional"))
      (node (ref "U4") (pin "60") (pinfunction "VSS(IO)2_60") (pintype "bidirectional"))
      (node (ref "U4") (pin "63") (pinfunction "VSS(IO/DCDC)_63") (pintype "bidirectional"))
      (node (ref "U4") (pin "66") (pinfunction "VCC_DCDC(IO/DCDC)_66") (pintype "bidirectional"))
      (node (ref "U4") (pin "83") (pinfunction "VSS(IO)3_83") (pintype "bidirectional"))
      (node (ref "U4") (pin "98") (pinfunction "VSS(IO)4_98") (pintype "bidirectional"))
      (node (ref "X4") (pin "2") (pinfunction "2_2") (pintype "bidirectional"))
      (node (ref "X4") (pin "4") (pinfunction "4_4") (pintype "bidirectional"))
    )
    (net (code "17") (name "GNDE") (class "Default")
      (node (ref "J1") (pin "P$4") (pinfunction "P$4_P$4") (pintype "bidirectional"))
      (node (ref "J2") (pin "P$6") (pinfunction "SHIELD1_P$6") (pintype "bidirectional"))
      (node (ref "J2") (pin "P$7") (pinfunction "SHIELD2_P$7") (pintype "bidirectional"))
      (node (ref "J2") (pin "P$8") (pinfunction "SHIELD3_P$8") (pintype "bidirectional"))
      (node (ref "J2") (pin "P$9") (pinfunction "SHIELD4_P$9") (pintype "bidirectional"))
      (node (ref "J3") (pin "SHLD1") (pinfunction "SHIELD_1_SHLD1") (pintype "bidirectional"))
      (node (ref "J3") (pin "SHLD2") (pinfunction "SHIELD_2_SHLD2") (pintype "bidirectional"))
      (node (ref "J4") (pin "13") (pinfunction "GNDE0_13") (pintype "bidirectional"))
      (node (ref "J4") (pin "14") (pinfunction "GNDE1_14") (pintype "bidirectional"))
      (node (ref "J9") (pin "S1") (pinfunction "SHIELD_S1") (pintype "passive"))
      (node (ref "J9") (pin "S2") (pinfunction "SHIELD_S2") (pintype "passive"))
      (node (ref "J9") (pin "S3") (pinfunction "SHIELD_S3") (pintype "passive"))
      (node (ref "J9") (pin "S4") (pinfunction "SHIELD_S4") (pintype "passive"))
    )
    (net (code "18") (name "ID") (class "Default")
      (node (ref "J2") (pin "P$4") (pinfunction "ID_P$4") (pintype "bidirectional"))
    )
    (net (code "19") (name "IIC_1_SCL") (class "Default")
      (node (ref "J10") (pin "P$5") (pinfunction "P$5_P$5") (pintype "bidirectional"))
      (node (ref "R20") (pin "P$2") (pinfunction "2_P$2") (pintype "passive"))
      (node (ref "U4") (pin "132") (pinfunction "P1_0_132") (pintype "bidirectional"))
    )
    (net (code "20") (name "IIC_1_SDA") (class "Default")
      (node (ref "J10") (pin "P$6") (pinfunction "P$6_P$6") (pintype "bidirectional"))
      (node (ref "R21") (pin "P$2") (pinfunction "2_P$2") (pintype "passive"))
      (node (ref "U4") (pin "131") (pinfunction "P1_1_131") (pintype "bidirectional"))
    )
    (net (code "21") (name "INT_MI_01") (class "Default")
      (node (ref "J10") (pin "P$39") (pinfunction "P$39_P$39") (pintype "bidirectional"))
      (node (ref "U4") (pin "87") (pinfunction "P3_1_87") (pintype "bidirectional"))
    )
    (net (code "22") (name "INT_MI_02") (class "Default")
      (node (ref "J10") (pin "P$40") (pinfunction "P$40_P$40") (pintype "bidirectional"))
      (node (ref "U4") (pin "86") (pinfunction "P3_2_86") (pintype "bidirectional"))
    )
    (net (code "23") (name "INT_MI_03") (class "Default")
      (node (ref "J10") (pin "P$9") (pinfunction "P$9_P$9") (pintype "bidirectional"))
      (node (ref "U4") (pin "128") (pinfunction "P1_4_128") (pintype "bidirectional"))
    )
    (net (code "24") (name "INT_MI_04") (class "Default")
      (node (ref "J10") (pin "P$10") (pinfunction "P$10_P$10") (pintype "bidirectional"))
      (node (ref "U4") (pin "127") (pinfunction "P1_5_127") (pintype "bidirectional"))
    )
    (net (code "25") (name "LED1{slash}SPEED") (class "Default")
      (node (ref "J4") (pin "11") (pinfunction "YLO_11") (pintype "bidirectional"))
      (node (ref "U3") (pin "23") (pinfunction "LED0/ANEN_SPEED_23") (pintype "bidirectional"))
    )
    (net (code "26") (name "NC") (class "Default")
      (node (ref "J4") (pin "7") (pinfunction "P7_7") (pintype "bidirectional"))
    )
    (net (code "27") (name "Net-(C16-1)") (class "Default")
      (node (ref "C16") (pin "P$1") (pinfunction "1_P$1") (pintype "passive"))
      (node (ref "J2") (pin "P$1") (pinfunction "VBUS_P$1") (pintype "bidirectional"))
      (node (ref "R4") (pin "P$2") (pinfunction "2_P$2") (pintype "passive"))
      (node (ref "R7") (pin "P$2") (pinfunction "2_P$2") (pintype "passive"))
    )
    (net (code "28") (name "Net-(C31-1)") (class "Default")
      (node (ref "C31") (pin "P$1") (pinfunction "1_P$1") (pintype "passive"))
      (node (ref "U4") (pin "62") (pinfunction "VCL1_62") (pintype "bidirectional"))
    )
    (net (code "29") (name "Net-(C37-2)") (class "Default")
      (node (ref "C37") (pin "P$2") (pinfunction "2_P$2") (pintype "passive"))
      (node (ref "U4") (pin "148") (pinfunction "VCL2_148") (pintype "bidirectional"))
    )
    (net (code "30") (name "Net-(C38-1)") (class "Default")
      (node (ref "C38") (pin "P$1") (pinfunction "1_P$1") (pintype "passive"))
      (node (ref "U4") (pin "19") (pinfunction "VCLO_19") (pintype "bidirectional"))
    )
    (net (code "31") (name "Net-(C44-1)") (class "Default")
      (node (ref "C43") (pin "1") (pinfunction "1_1") (pintype "passive"))
      (node (ref "C44") (pin "P$1") (pinfunction "1_P$1") (pintype "passive"))
      (node (ref "FB2/2") (pin "2") (pinfunction "P$2_2") (pintype "bidirectional"))
      (node (ref "U3") (pin "2") (pinfunction "VDDA_3.3_2") (pintype "power_in"))
    )
    (net (code "32") (name "Net-(J2-D+)") (class "Default")
      (node (ref "J2") (pin "P$3") (pinfunction "D+_P$3") (pintype "bidirectional"))
      (node (ref "R6") (pin "P$2") (pinfunction "2_P$2") (pintype "passive"))
    )
    (net (code "33") (name "Net-(J2-D-)") (class "Default")
      (node (ref "J2") (pin "P$2") (pinfunction "D-_P$2") (pintype "bidirectional"))
      (node (ref "R5") (pin "P$2") (pinfunction "2_P$2") (pintype "passive"))
    )
    (net (code "34") (name "Net-(R13-1)") (class "Default")
      (node (ref "LED3") (pin "A") (pinfunction "A_A") (pintype "passive"))
      (node (ref "R13") (pin "P$1") (pinfunction "1_P$1") (pintype "passive"))
    )
    (net (code "35") (name "Net-(R16-2)") (class "Default")
      (node (ref "R16") (pin "P$2") (pinfunction "2_P$2") (pintype "passive"))
      (node (ref "U4") (pin "65") (pinfunction "VLO2(DCDC)_65") (pintype "bidirectional"))
    )
    (net (code "36") (name "Net-(R17-2)") (class "Default")
      (node (ref "R17") (pin "P$2") (pinfunction "2_P$2") (pintype "passive"))
      (node (ref "U4") (pin "64") (pinfunction "VLO1(DCDC)_64") (pintype "bidirectional"))
    )
    (net (code "37") (name "Net-(R19-2)") (class "Default")
      (node (ref "R19") (pin "P$2") (pinfunction "2_P$2") (pintype "passive"))
      (node (ref "U4") (pin "27") (pinfunction "USBHS_RREF_27") (pintype "bidirectional"))
    )
    (net (code "38") (name "P0_00") (class "Default")
      (node (ref "J5") (pin "P$2") (pinfunction "P$2_P$2") (pintype "bidirectional"))
      (node (ref "U4") (pin "169") (pinfunction "P0_0/AN0\\00_169") (pintype "bidirectional"))
    )
    (net (code "39") (name "P0_01") (class "Default")
      (node (ref "J5") (pin "P$1") (pinfunction "P$1_P$1") (pintype "bidirectional"))
      (node (ref "U4") (pin "168") (pinfunction "P0_1/AN001_168") (pintype "bidirectional"))
    )
    (net (code "40") (name "P0_02") (class "Default")
      (node (ref "J12") (pin "1") (pinfunction "1_1") (pintype "passive"))
      (node (ref "U4") (pin "167") (pinfunction "P0_2/AN002_167") (pintype "bidirectional"))
    )
    (net (code "41") (name "P0_03") (class "Default")
      (node (ref "J12") (pin "3") (pinfunction "3_3") (pintype "passive"))
      (node (ref "U4") (pin "166") (pinfunction "P0_3/PGAVSS000_166") (pintype "bidirectional"))
    )
    (net (code "42") (name "P0_04") (class "Default")
      (node (ref "J12") (pin "5") (pinfunction "5_5") (pintype "passive"))
      (node (ref "U4") (pin "165") (pinfunction "P0_4/AN100_165") (pintype "bidirectional"))
    )
    (net (code "43") (name "P0_05") (class "Default")
      (node (ref "J12") (pin "7") (pinfunction "7_7") (pintype "passive"))
      (node (ref "U4") (pin "164") (pinfunction "P0_5/AN101_164") (pintype "bidirectional"))
    )
    (net (code "44") (name "P0_06") (class "Default")
      (node (ref "J12") (pin "9") (pinfunction "9_9") (pintype "passive"))
      (node (ref "U4") (pin "163") (pinfunction "P0_6/AN102_163") (pintype "bidirectional"))
    )
    (net (code "45") (name "P0_07") (class "Default")
      (node (ref "J12") (pin "10") (pinfunction "10_10") (pintype "passive"))
      (node (ref "U4") (pin "162") (pinfunction "P0_7/PGVSS100_162") (pintype "bidirectional"))
    )
    (net (code "46") (name "P0_08") (class "Default")
      (node (ref "J12") (pin "8") (pinfunction "8_8") (pintype "passive"))
      (node (ref "U4") (pin "161") (pinfunction "P0_8/AN003_161") (pintype "bidirectional"))
    )
    (net (code "47") (name "P0_09") (class "Default")
      (node (ref "J12") (pin "6") (pinfunction "6_6") (pintype "passive"))
      (node (ref "U4") (pin "160") (pinfunction "P0_9/AN004_160") (pintype "bidirectional"))
    )
    (net (code "48") (name "P0_14") (class "Default")
      (node (ref "J12") (pin "4") (pinfunction "4_4") (pintype "passive"))
      (node (ref "U4") (pin "152") (pinfunction "P0_14/DA0/AN005/AN105_152") (pintype "bidirectional"))
    )
    (net (code "49") (name "P0_15") (class "Default")
      (node (ref "J12") (pin "2") (pinfunction "2_2") (pintype "passive"))
      (node (ref "U4") (pin "151") (pinfunction "P0_15/DA1/AN006/AN106_151") (pintype "bidirectional"))
    )
    (net (code "50") (name "P1_02") (class "Default")
      (node (ref "J10") (pin "P$7") (pinfunction "P$7_P$7") (pintype "bidirectional"))
      (node (ref "U4") (pin "130") (pinfunction "P1_2_130") (pintype "bidirectional"))
    )
    (net (code "51") (name "P1_03") (class "Default")
      (node (ref "J10") (pin "P$8") (pinfunction "P$8_P$8") (pintype "bidirectional"))
      (node (ref "U4") (pin "129") (pinfunction "P1_3_129") (pintype "bidirectional"))
    )
    (net (code "52") (name "P1_06") (class "Default")
      (node (ref "J10") (pin "P$11") (pinfunction "P$11_P$11") (pintype "bidirectional"))
      (node (ref "U4") (pin "126") (pinfunction "P1_6_126") (pintype "bidirectional"))
    )
    (net (code "53") (name "P1_07") (class "Default")
      (node (ref "J10") (pin "P$12") (pinfunction "P$12_P$12") (pintype "bidirectional"))
      (node (ref "U4") (pin "125") (pinfunction "P1_7_125") (pintype "bidirectional"))
    )
    (net (code "54") (name "P1_11") (class "Default")
      (node (ref "J10") (pin "P$38") (pinfunction "P$38_P$38") (pintype "bidirectional"))
      (node (ref "U4") (pin "92") (pinfunction "P1_11_92") (pintype "bidirectional"))
    )
    (net (code "55") (name "P1_12") (class "Default")
      (node (ref "J10") (pin "P$37") (pinfunction "P$37_P$37") (pintype "bidirectional"))
      (node (ref "U4") (pin "93") (pinfunction "P1_12_93") (pintype "bidirectional"))
    )
    (net (code "56") (name "P1_13") (class "Default")
      (node (ref "J10") (pin "P$36") (pinfunction "P$36_P$36") (pintype "bidirectional"))
      (node (ref "U4") (pin "94") (pinfunction "P1_13_94") (pintype "bidirectional"))
    )
    (net (code "57") (name "P1_14") (class "Default")
      (node (ref "J10") (pin "P$35") (pinfunction "P$35_P$35") (pintype "bidirectional"))
      (node (ref "U4") (pin "95") (pinfunction "P1_14_95") (pintype "bidirectional"))
    )
    (net (code "58") (name "P1_15") (class "Default")
      (node (ref "J10") (pin "P$34") (pinfunction "P$34_P$34") (pintype "bidirectional"))
      (node (ref "U4") (pin "96") (pinfunction "P1_15_96") (pintype "bidirectional"))
    )
    (net (code "59") (name "P2_00") (class "Default")
      (node (ref "J7") (pin "P$13") (pinfunction "P$13_P$13") (pintype "bidirectional"))
      (node (ref "U4") (pin "69") (pinfunction "P2_0(INPUT_ONLY)_69") (pintype "bidirectional"))
    )
    (net (code "60") (name "P2_01") (class "Default")
      (node (ref "J7") (pin "P$14") (pinfunction "P$14_P$14") (pintype "bidirectional"))
      (node (ref "U4") (pin "68") (pinfunction "P2_1/MD_68") (pintype "bidirectional"))
    )
    (net (code "61") (name "P2_02") (class "Default")
      (node (ref "J7") (pin "P$19") (pinfunction "P$19_P$19") (pintype "bidirectional"))
      (node (ref "U4") (pin "54") (pinfunction "P2_2_54") (pintype "bidirectional"))
    )
    (net (code "62") (name "P2_03") (class "Default")
      (node (ref "J6") (pin "1") (pinfunction "1_1") (pintype "passive"))
      (node (ref "U4") (pin "53") (pinfunction "P2_3_53") (pintype "bidirectional"))
    )
    (net (code "63") (name "P2_04") (class "Default")
      (node (ref "J6") (pin "3") (pinfunction "3_3") (pintype "passive"))
      (node (ref "U4") (pin "52") (pinfunction "P2_4_52") (pintype "bidirectional"))
    )
    (net (code "64") (name "P2_05") (class "Default")
      (node (ref "J6") (pin "5") (pinfunction "5_5") (pintype "passive"))
      (node (ref "U4") (pin "51") (pinfunction "P2_5_51") (pintype "bidirectional"))
    )
    (net (code "65") (name "P2_06") (class "Default")
      (node (ref "J6") (pin "7") (pinfunction "7_7") (pintype "passive"))
      (node (ref "U4") (pin "50") (pinfunction "P2_6_50") (pintype "bidirectional"))
    )
    (net (code "66") (name "P2_07") (class "Default")
      (node (ref "J6") (pin "9") (pinfunction "9_9") (pintype "passive"))
      (node (ref "U4") (pin "49") (pinfunction "P2_7_49") (pintype "bidirectional"))
    )
    (net (code "67") (name "P3_03") (class "Default")
      (node (ref "J7") (pin "P$2") (pinfunction "P$2_P$2") (pintype "bidirectional"))
      (node (ref "U4") (pin "85") (pinfunction "P3_3_85") (pintype "bidirectional"))
    )
    (net (code "68") (name "P3_04") (class "Default")
      (node (ref "J7") (pin "P$4") (pinfunction "P$4_P$4") (pintype "bidirectional"))
      (node (ref "U4") (pin "82") (pinfunction "P3_4_82") (pintype "bidirectional"))
    )
    (net (code "69") (name "P3_05") (class "Default")
      (node (ref "J7") (pin "P$6") (pinfunction "P$6_P$6") (pintype "bidirectional"))
      (node (ref "U4") (pin "81") (pinfunction "P3_5_81") (pintype "bidirectional"))
    )
    (net (code "70") (name "P3_06") (class "Default")
      (node (ref "J7") (pin "P$1") (pinfunction "P$1_P$1") (pintype "bidirectional"))
      (node (ref "U4") (pin "80") (pinfunction "P3_6_80") (pintype "bidirectional"))
    )
    (net (code "71") (name "P3_07") (class "Default")
      (node (ref "J7") (pin "P$3") (pinfunction "P$3_P$3") (pintype "bidirectional"))
      (node (ref "U4") (pin "79") (pinfunction "P3_7_79") (pintype "bidirectional"))
    )
    (net (code "72") (name "P3_09") (class "Default")
      (node (ref "J7") (pin "P$5") (pinfunction "P$5_P$5") (pintype "bidirectional"))
      (node (ref "U4") (pin "77") (pinfunction "P3_9_77") (pintype "bidirectional"))
    )
    (net (code "73") (name "P3_10") (class "Default")
      (node (ref "J7") (pin "P$7") (pinfunction "P$7_P$7") (pintype "bidirectional"))
      (node (ref "U4") (pin "76") (pinfunction "P3_10_76") (pintype "bidirectional"))
    )
    (net (code "74") (name "P3_11") (class "Default")
      (node (ref "J7") (pin "P$8") (pinfunction "P$8_P$8") (pintype "bidirectional"))
      (node (ref "U4") (pin "75") (pinfunction "P3_11_75") (pintype "bidirectional"))
    )
    (net (code "75") (name "P3_12") (class "Default")
      (node (ref "J7") (pin "P$9") (pinfunction "P$9_P$9") (pintype "bidirectional"))
      (node (ref "U4") (pin "74") (pinfunction "P3_12_74") (pintype "bidirectional"))
    )
    (net (code "76") (name "P3_13") (class "Default")
      (node (ref "J7") (pin "P$20") (pinfunction "P$20_P$20") (pintype "bidirectional"))
      (node (ref "U4") (pin "55") (pinfunction "P3_13_55") (pintype "bidirectional"))
    )
    (net (code "77") (name "P3_14") (class "Default")
      (node (ref "J7") (pin "P$17") (pinfunction "P$17_P$17") (pintype "bidirectional"))
      (node (ref "U4") (pin "56") (pinfunction "P3_14_56") (pintype "bidirectional"))
    )
    (net (code "78") (name "P3_15") (class "Default")
      (node (ref "J7") (pin "P$18") (pinfunction "P$18_P$18") (pintype "bidirectional"))
      (node (ref "U4") (pin "57") (pinfunction "P3_15_57") (pintype "bidirectional"))
    )
    (net (code "79") (name "P4_00") (class "Default")
      (node (ref "J5") (pin "P$7") (pinfunction "P$7_P$7") (pintype "bidirectional"))
      (node (ref "U4") (pin "1") (pinfunction "P4_0_1") (pintype "bidirectional"))
    )
    (net (code "80") (name "P4_01") (class "Default")
      (node (ref "J5") (pin "P$8") (pinfunction "P$8_P$8") (pintype "bidirectional"))
      (node (ref "U4") (pin "2") (pinfunction "P4_1_2") (pintype "bidirectional"))
    )
    (net (code "81") (name "P4_02") (class "Default")
      (node (ref "J5") (pin "P$9") (pinfunction "P$9_P$9") (pintype "bidirectional"))
      (node (ref "U4") (pin "3") (pinfunction "P4_2_3") (pintype "bidirectional"))
    )
    (net (code "82") (name "P4_08") (class "Default")
      (node (ref "J5") (pin "P$20") (pinfunction "P$20_P$20") (pintype "bidirectional"))
      (node (ref "U4") (pin "43") (pinfunction "P4_8_43") (pintype "bidirectional"))
    )
    (net (code "83") (name "P4_09") (class "Default")
      (node (ref "J5") (pin "P$19") (pinfunction "P$19_P$19") (pintype "bidirectional"))
      (node (ref "U4") (pin "42") (pinfunction "P4_9_42") (pintype "bidirectional"))
    )
    (net (code "84") (name "P4_10") (class "Default")
      (node (ref "J5") (pin "P$18") (pinfunction "P$18_P$18") (pintype "bidirectional"))
      (node (ref "U4") (pin "41") (pinfunction "P4_10_41") (pintype "bidirectional"))
    )
    (net (code "85") (name "P4_11") (class "Default")
      (node (ref "J5") (pin "P$17") (pinfunction "P$17_P$17") (pintype "bidirectional"))
      (node (ref "U4") (pin "40") (pinfunction "P4_11_40") (pintype "bidirectional"))
    )
    (net (code "86") (name "P4_12") (class "Default")
      (node (ref "J5") (pin "P$16") (pinfunction "P$16_P$16") (pintype "bidirectional"))
      (node (ref "U4") (pin "39") (pinfunction "P4_12_39") (pintype "bidirectional"))
    )
    (net (code "87") (name "P4_13") (class "Default")
      (node (ref "J5") (pin "P$15") (pinfunction "P$15_P$15") (pintype "bidirectional"))
      (node (ref "U4") (pin "38") (pinfunction "P4_13_38") (pintype "bidirectional"))
    )
    (net (code "88") (name "P4_14") (class "Default")
      (node (ref "J5") (pin "P$14") (pinfunction "P$14_P$14") (pintype "bidirectional"))
      (node (ref "U4") (pin "37") (pinfunction "P4_14_37") (pintype "bidirectional"))
    )
    (net (code "89") (name "P4_15") (class "Default")
      (node (ref "J5") (pin "P$13") (pinfunction "P$13_P$13") (pintype "bidirectional"))
      (node (ref "U4") (pin "36") (pinfunction "P4_15_36") (pintype "bidirectional"))
    )
    (net (code "90") (name "P5_11") (class "Default")
      (node (ref "J5") (pin "P$6") (pinfunction "P$6_P$6") (pintype "bidirectional"))
      (node (ref "U4") (pin "176") (pinfunction "P5_11_176") (pintype "bidirectional"))
    )
    (net (code "91") (name "P5_12") (class "Default")
      (node (ref "J5") (pin "P$5") (pinfunction "P$5_P$5") (pintype "bidirectional"))
      (node (ref "U4") (pin "175") (pinfunction "P5_12_175") (pintype "bidirectional"))
    )
    (net (code "92") (name "P5_13") (class "Default")
      (node (ref "J5") (pin "P$4") (pinfunction "P$4_P$4") (pintype "bidirectional"))
      (node (ref "U4") (pin "174") (pinfunction "P5_13_174") (pintype "bidirectional"))
    )
    (net (code "93") (name "P6_00") (class "Default")
      (node (ref "J10") (pin "P$13") (pinfunction "P$13_P$13") (pintype "bidirectional"))
      (node (ref "U4") (pin "122") (pinfunction "P6_0_122") (pintype "bidirectional"))
    )
    (net (code "94") (name "P6_01") (class "Default")
      (node (ref "J10") (pin "P$14") (pinfunction "P$14_P$14") (pintype "bidirectional"))
      (node (ref "U4") (pin "121") (pinfunction "P6_1_121") (pintype "bidirectional"))
    )
    (net (code "95") (name "P6_02") (class "Default")
      (node (ref "J10") (pin "P$15") (pinfunction "P$15_P$15") (pintype "bidirectional"))
      (node (ref "U4") (pin "120") (pinfunction "P6_2_120") (pintype "bidirectional"))
    )
    (net (code "96") (name "P6_03") (class "Default")
      (node (ref "J10") (pin "P$16") (pinfunction "P$16_P$16") (pintype "bidirectional"))
      (node (ref "U4") (pin "119") (pinfunction "P6_3_119") (pintype "bidirectional"))
    )
    (net (code "97") (name "P6_04") (class "Default")
      (node (ref "J10") (pin "P$17") (pinfunction "P$17_P$17") (pintype "bidirectional"))
      (node (ref "U4") (pin "118") (pinfunction "P6_4_118") (pintype "bidirectional"))
    )
    (net (code "98") (name "P6_05") (class "Default")
      (node (ref "J10") (pin "P$18") (pinfunction "P$18_P$18") (pintype "bidirectional"))
      (node (ref "U4") (pin "117") (pinfunction "P6_5_117") (pintype "bidirectional"))
    )
    (net (code "99") (name "P6_06") (class "Default")
      (node (ref "J10") (pin "P$19") (pinfunction "P$19_P$19") (pintype "bidirectional"))
      (node (ref "U4") (pin "116") (pinfunction "P6_6_116") (pintype "bidirectional"))
    )
    (net (code "100") (name "P6_07") (class "Default")
      (node (ref "J10") (pin "P$20") (pinfunction "P$20_P$20") (pintype "bidirectional"))
      (node (ref "U4") (pin "115") (pinfunction "P6_7_115") (pintype "bidirectional"))
    )
    (net (code "101") (name "P6_08") (class "Default")
      (node (ref "J10") (pin "P$33") (pinfunction "P$33_P$33") (pintype "bidirectional"))
      (node (ref "U4") (pin "99") (pinfunction "P6_8_99") (pintype "bidirectional"))
    )
    (net (code "102") (name "P6_09") (class "Default")
      (node (ref "J10") (pin "P$32") (pinfunction "P$32_P$32") (pintype "bidirectional"))
      (node (ref "U4") (pin "100") (pinfunction "P6_9_100") (pintype "bidirectional"))
    )
    (net (code "103") (name "P6_10") (class "Default")
      (node (ref "J10") (pin "P$31") (pinfunction "P$31_P$31") (pintype "bidirectional"))
      (node (ref "U4") (pin "101") (pinfunction "P6_10_101") (pintype "bidirectional"))
    )
    (net (code "104") (name "P6_11") (class "Default")
      (node (ref "J10") (pin "P$30") (pinfunction "P$30_P$30") (pintype "bidirectional"))
      (node (ref "U4") (pin "102") (pinfunction "P6_11_102") (pintype "bidirectional"))
    )
    (net (code "105") (name "P6_12") (class "Default")
      (node (ref "J10") (pin "P$29") (pinfunction "P$29_P$29") (pintype "bidirectional"))
      (node (ref "U4") (pin "103") (pinfunction "P6_12_103") (pintype "bidirectional"))
    )
    (net (code "106") (name "P6_13") (class "Default")
      (node (ref "J10") (pin "P$28") (pinfunction "P$28_P$28") (pintype "bidirectional"))
      (node (ref "U4") (pin "104") (pinfunction "P6_13_104") (pintype "bidirectional"))
    )
    (net (code "107") (name "P6_14") (class "Default")
      (node (ref "J10") (pin "P$27") (pinfunction "P$27_P$27") (pintype "bidirectional"))
      (node (ref "U4") (pin "105") (pinfunction "P6_14_105") (pintype "bidirectional"))
    )
    (net (code "108") (name "P6_15") (class "Default")
      (node (ref "J10") (pin "P$26") (pinfunction "P$26_P$26") (pintype "bidirectional"))
      (node (ref "U4") (pin "106") (pinfunction "P6_15_106") (pintype "bidirectional"))
    )
    (net (code "109") (name "P7_06") (class "Default")
      (node (ref "J5") (pin "P$10") (pinfunction "P$10_P$10") (pintype "bidirectional"))
      (node (ref "U4") (pin "14") (pinfunction "P7_6_14") (pintype "bidirectional"))
    )
    (net (code "110") (name "P7_07") (class "Default")
      (node (ref "J5") (pin "P$11") (pinfunction "P$11_P$11") (pintype "bidirectional"))
      (node (ref "U4") (pin "15") (pinfunction "P7_7_15") (pintype "bidirectional"))
    )
    (net (code "111") (name "P8_00") (class "Default")
      (node (ref "J10") (pin "P$4") (pinfunction "P$4_P$4") (pintype "bidirectional"))
      (node (ref "U4") (pin "133") (pinfunction "P8_0_133") (pintype "bidirectional"))
    )
    (net (code "112") (name "P8_01") (class "Default")
      (node (ref "J10") (pin "P$3") (pinfunction "P$3_P$3") (pintype "bidirectional"))
      (node (ref "U4") (pin "134") (pinfunction "P8_1_134") (pintype "bidirectional"))
    )
    (net (code "113") (name "P8_02") (class "Default")
      (node (ref "J10") (pin "P$2") (pinfunction "P$2_P$2") (pintype "bidirectional"))
      (node (ref "U4") (pin "135") (pinfunction "P8_2_135") (pintype "bidirectional"))
    )
    (net (code "114") (name "P8_03") (class "Default")
      (node (ref "U4") (pin "136") (pinfunction "P8_3_136") (pintype "bidirectional"))
    )
    (net (code "115") (name "P8_04") (class "Default")
      (node (ref "U4") (pin "137") (pinfunction "P8_4_137") (pintype "bidirectional"))
    )
    (net (code "116") (name "P8_05") (class "Default")
      (node (ref "J5") (pin "P$3") (pinfunction "P$3_P$3") (pintype "bidirectional"))
      (node (ref "U4") (pin "173") (pinfunction "P8_5_173") (pintype "bidirectional"))
    )
    (net (code "117") (name "P9_00") (class "Default")
      (node (ref "J7") (pin "P$16") (pinfunction "P$16_P$16") (pintype "bidirectional"))
      (node (ref "U4") (pin "58") (pinfunction "P9_0_58") (pintype "bidirectional"))
    )
    (net (code "118") (name "P9_01") (class "Default")
      (node (ref "J7") (pin "P$15") (pinfunction "P$15_P$15") (pintype "bidirectional"))
      (node (ref "U4") (pin "59") (pinfunction "P9_1_59") (pintype "bidirectional"))
    )
    (net (code "119") (name "P9_05") (class "Default")
      (node (ref "J7") (pin "P$10") (pinfunction "P$10_P$10") (pintype "bidirectional"))
      (node (ref "U4") (pin "73") (pinfunction "P9_5_73") (pintype "bidirectional"))
    )
    (net (code "120") (name "P9_06") (class "Default")
      (node (ref "J7") (pin "P$11") (pinfunction "P$11_P$11") (pintype "bidirectional"))
      (node (ref "U4") (pin "72") (pinfunction "P9_6_72") (pintype "bidirectional"))
    )
    (net (code "121") (name "P9_07") (class "Default")
      (node (ref "J7") (pin "P$12") (pinfunction "P$12_P$12") (pintype "bidirectional"))
      (node (ref "U4") (pin "71") (pinfunction "P9_7_71") (pintype "bidirectional"))
    )
    (net (code "122") (name "P9_08") (class "Default")
      (node (ref "U4") (pin "70") (pinfunction "P9_8_70") (pintype "bidirectional"))
    )
    (net (code "123") (name "PA_00") (class "Default")
      (node (ref "J10") (pin "P$21") (pinfunction "P$21_P$21") (pintype "bidirectional"))
      (node (ref "U4") (pin "114") (pinfunction "PA_0_114") (pintype "bidirectional"))
    )
    (net (code "124") (name "PA_01") (class "Default")
      (node (ref "J10") (pin "P$22") (pinfunction "P$22_P$22") (pintype "bidirectional"))
      (node (ref "U4") (pin "113") (pinfunction "PA_1_113") (pintype "bidirectional"))
    )
    (net (code "125") (name "PA_08") (class "Default")
      (node (ref "J10") (pin "P$25") (pinfunction "P$25_P$25") (pintype "bidirectional"))
      (node (ref "U4") (pin "107") (pinfunction "PA_8_107") (pintype "bidirectional"))
    )
    (net (code "126") (name "PA_09") (class "Default")
      (node (ref "J10") (pin "P$24") (pinfunction "P$24_P$24") (pintype "bidirectional"))
      (node (ref "U4") (pin "108") (pinfunction "PA_9_108") (pintype "bidirectional"))
    )
    (net (code "127") (name "PA_10") (class "Default")
      (node (ref "J10") (pin "P$23") (pinfunction "P$23_P$23") (pintype "bidirectional"))
      (node (ref "U4") (pin "109") (pinfunction "PA_10_109") (pintype "bidirectional"))
    )
    (net (code "128") (name "PB_00") (class "Default")
      (node (ref "J5") (pin "P$12") (pinfunction "P$12_P$12") (pintype "bidirectional"))
      (node (ref "U4") (pin "16") (pinfunction "PB_0_16") (pintype "bidirectional"))
    )
    (net (code "129") (name "R51") (class "Default")
      (node (ref "J4") (pin "12") (pinfunction "YHI_12") (pintype "bidirectional"))
      (node (ref "R23") (pin "P$1") (pinfunction "1_P$1") (pintype "passive"))
    )
    (net (code "130") (name "R52") (class "Default")
      (node (ref "J4") (pin "9") (pinfunction "GHI_9") (pintype "bidirectional"))
      (node (ref "R24") (pin "P$1") (pinfunction "1_P$1") (pintype "passive"))
    )
    (net (code "131") (name "RESET") (class "Default")
      (node (ref "C57") (pin "P$1") (pinfunction "1_P$1") (pintype "passive"))
      (node (ref "J11") (pin "9") (pinfunction "9_9") (pintype "passive"))
      (node (ref "R18") (pin "P$1") (pinfunction "1_P$1") (pintype "passive"))
      (node (ref "U4") (pin "67") (pinfunction "RES#_67") (pintype "bidirectional"))
    )
    (net (code "132") (name "REXT") (class "Default")
      (node (ref "C47") (pin "P$1") (pinfunction "1_P$1") (pintype "passive"))
      (node (ref "R25") (pin "P$2") (pinfunction "2_P$2") (pintype "passive"))
      (node (ref "U3") (pin "9") (pinfunction "REXT_9") (pintype "input"))
    )
    (net (code "133") (name "RXD0") (class "Default")
      (node (ref "R31") (pin "P$2") (pinfunction "2_P$2") (pintype "passive"))
      (node (ref "U3") (pin "13") (pinfunction "RXD0_13") (pintype "bidirectional"))
    )
    (net (code "134") (name "RXD1") (class "Default")
      (node (ref "R30") (pin "P$2") (pinfunction "2_P$2") (pintype "passive"))
      (node (ref "U3") (pin "12") (pinfunction "RXD1_12") (pintype "bidirectional"))
    )
    (net (code "135") (name "RXER") (class "Default")
      (node (ref "R32") (pin "P$2") (pinfunction "2_P$2") (pintype "passive"))
      (node (ref "U3") (pin "17") (pinfunction "RXER_17") (pintype "bidirectional"))
    )
    (net (code "136") (name "RXM") (class "Default")
      (node (ref "J4") (pin "6") (pinfunction "RD-_6") (pintype "bidirectional"))
      (node (ref "U3") (pin "3") (pinfunction "RXM_3") (pintype "bidirectional"))
    )
    (net (code "137") (name "RXP") (class "Default")
      (node (ref "J4") (pin "3") (pinfunction "RD+_3") (pintype "bidirectional"))
      (node (ref "U3") (pin "4") (pinfunction "RXP_4") (pintype "bidirectional"))
    )
    (net (code "138") (name "SD1_CD") (class "Default")
      (node (ref "J9") (pin "10") (pinfunction "CD_SWITCH2_10") (pintype "bidirectional"))
      (node (ref "U4") (pin "146") (pinfunction "P5_6/AN019_146") (pintype "bidirectional"))
    )
    (net (code "139") (name "SD1_CLK") (class "Default")
      (node (ref "J9") (pin "5") (pinfunction "CLOCK_5") (pintype "bidirectional"))
      (node (ref "U4") (pin "140") (pinfunction "P5_0/AN016_140") (pintype "bidirectional"))
    )
    (net (code "140") (name "SD1_CMD") (class "Default")
      (node (ref "J9") (pin "3") (pinfunction "COMMAND/RESPONSE_3") (pintype "bidirectional"))
      (node (ref "U4") (pin "141") (pinfunction "P5_1/AN116_141") (pintype "bidirectional"))
    )
    (net (code "141") (name "SD1_DAT0") (class "Default")
      (node (ref "J9") (pin "7") (pinfunction "DATA_LINE[BIT_0]_7") (pintype "bidirectional"))
      (node (ref "U4") (pin "142") (pinfunction "P5_2/AN017_142") (pintype "bidirectional"))
    )
    (net (code "142") (name "SD1_DAT1") (class "Default")
      (node (ref "J9") (pin "8") (pinfunction "DATA_LINE[BIT_1]_8") (pintype "bidirectional"))
      (node (ref "U4") (pin "143") (pinfunction "P5_3/AN117_143") (pintype "bidirectional"))
    )
    (net (code "143") (name "SD1_DAT2") (class "Default")
      (node (ref "J9") (pin "1") (pinfunction "DATA_LINE[BIT_2]_1") (pintype "bidirectional"))
      (node (ref "U4") (pin "144") (pinfunction "P5_4/AN018_144") (pintype "bidirectional"))
    )
    (net (code "144") (name "SD1_DAT3") (class "Default")
      (node (ref "J9") (pin "2") (pinfunction "CARD_DETECT/DATA_LINE[BIT_3]_2") (pintype "bidirectional"))
      (node (ref "U4") (pin "145") (pinfunction "P5_5/AN118_145") (pintype "bidirectional"))
    )
    (net (code "145") (name "SD1_WP") (class "Default")
      (node (ref "J9") (pin "9") (pinfunction "CD_SWITCH1_9") (pintype "bidirectional"))
      (node (ref "U4") (pin "147") (pinfunction "P5_7/AN119_147") (pintype "bidirectional"))
    )
    (net (code "146") (name "TCK") (class "Default")
      (node (ref "J11") (pin "7") (pinfunction "7_7") (pintype "passive"))
      (node (ref "U4") (pin "88") (pinfunction "P3_0_88") (pintype "bidirectional"))
    )
    (net (code "147") (name "TDI") (class "Default")
      (node (ref "J11") (pin "1") (pinfunction "1_1") (pintype "passive"))
      (node (ref "U4") (pin "91") (pinfunction "P1_10_91") (pintype "bidirectional"))
    )
    (net (code "148") (name "TDO") (class "Default")
      (node (ref "J11") (pin "3") (pinfunction "3_3") (pintype "passive"))
      (node (ref "U4") (pin "90") (pinfunction "P1_9_90") (pintype "bidirectional"))
    )
    (net (code "149") (name "TMS") (class "Default")
      (node (ref "J11") (pin "5") (pinfunction "5_5") (pintype "passive"))
      (node (ref "U4") (pin "89") (pinfunction "P1_8_89") (pintype "bidirectional"))
    )
    (net (code "150") (name "TXM") (class "Default")
      (node (ref "J4") (pin "2") (pinfunction "TD-_2") (pintype "bidirectional"))
      (node (ref "U3") (pin "5") (pinfunction "TXM_5") (pintype "bidirectional"))
    )
    (net (code "151") (name "TXP") (class "Default")
      (node (ref "J4") (pin "1") (pinfunction "TD+_1") (pintype "bidirectional"))
      (node (ref "U3") (pin "6") (pinfunction "TXP_6") (pintype "bidirectional"))
    )
    (net (code "152") (name "USBHS_FAULT") (class "Default")
      (node (ref "R12") (pin "P$1") (pinfunction "1_P$1") (pintype "passive"))
      (node (ref "U2") (pin "3") (pinfunction "FLG_3") (pintype "input"))
      (node (ref "U4") (pin "78") (pinfunction "P3_8_78") (pintype "bidirectional"))
    )
    (net (code "153") (name "USBHS_N") (class "Default")
      (node (ref "J3") (pin "D-") (pinfunction "D-_D-") (pintype "bidirectional"))
      (node (ref "U4") (pin "31") (pinfunction "USBHS_DM_31") (pintype "bidirectional"))
    )
    (net (code "154") (name "USBHS_P") (class "Default")
      (node (ref "J3") (pin "D+") (pinfunction "D+_D+") (pintype "bidirectional"))
      (node (ref "U4") (pin "32") (pinfunction "USBHS_DP_32") (pintype "bidirectional"))
    )
    (net (code "155") (name "USBHS_VBUS") (class "Default")
      (node (ref "C11") (pin "P$1") (pinfunction "1_P$1") (pintype "passive"))
      (node (ref "C15") (pin "1") (pinfunction "1_1") (pintype "passive"))
      (node (ref "J3") (pin "VBUS") (pinfunction "VBUS_VBUS") (pintype "power_in"))
      (node (ref "U2") (pin "5") (pinfunction "OUT_5") (pintype "input"))
      (node (ref "U4") (pin "17") (pinfunction "PB_1_17") (pintype "bidirectional"))
    )
    (net (code "156") (name "USBHS_VBUSEN") (class "Default")
      (node (ref "R1") (pin "P$1") (pinfunction "1_P$1") (pintype "passive"))
      (node (ref "U2") (pin "1") (pinfunction "EN_1") (pintype "input"))
    )
    (net (code "157") (name "USB_N") (class "Default")
      (node (ref "R5") (pin "P$1") (pinfunction "1_P$1") (pintype "passive"))
      (node (ref "U4") (pin "46") (pinfunction "USB_DM_46") (pintype "bidirectional"))
    )
    (net (code "158") (name "USB_P") (class "Default")
      (node (ref "R6") (pin "P$1") (pinfunction "1_P$1") (pintype "passive"))
      (node (ref "U4") (pin "47") (pinfunction "USB_DP_47") (pintype "bidirectional"))
    )
    (net (code "159") (name "USB_VBUS_B") (class "Default")
      (node (ref "R4") (pin "P$1") (pinfunction "1_P$1") (pintype "passive"))
      (node (ref "U4") (pin "44") (pinfunction "P4_7_44") (pintype "bidirectional"))
    )
    (net (code "160") (name "VCL_F(FLASH)") (class "Default")
      (node (ref "C36") (pin "P$2") (pinfunction "2_P$2") (pintype "passive"))
      (node (ref "U4") (pin "112") (pinfunction "VCL_F(FLASH)_112") (pintype "bidirectional"))
    )
    (net (code "161") (name "VDD") (class "Default")
      (node (ref "C1") (pin "P$2") (pinfunction "2_P$2") (pintype "passive"))
      (node (ref "C10") (pin "P$2") (pinfunction "2_P$2") (pintype "passive"))
      (node (ref "C13") (pin "P$2") (pinfunction "2_P$2") (pintype "passive"))
      (node (ref "C14") (pin "P$2") (pinfunction "2_P$2") (pintype "passive"))
      (node (ref "C2") (pin "P$2") (pinfunction "2_P$2") (pintype "passive"))
      (node (ref "C30") (pin "P$2") (pinfunction "2_P$2") (pintype "passive"))
      (node (ref "C32") (pin "P$1") (pinfunction "1_P$1") (pintype "passive"))
      (node (ref "C33") (pin "P$1") (pinfunction "1_P$1") (pintype "passive"))
      (node (ref "C34") (pin "P$1") (pinfunction "1_P$1") (pintype "passive"))
      (node (ref "C35") (pin "P$1") (pinfunction "1_P$1") (pintype "passive"))
      (node (ref "C48") (pin "1") (pinfunction "1_1") (pintype "passive"))
      (node (ref "C49") (pin "P$1") (pinfunction "1_P$1") (pintype "passive"))
      (node (ref "C54") (pin "P$2") (pinfunction "2_P$2") (pintype "passive"))
      (node (ref "C55") (pin "P$2") (pinfunction "2_P$2") (pintype "passive"))
      (node (ref "C56") (pin "P$2") (pinfunction "2_P$2") (pintype "passive"))
      (node (ref "C58") (pin "P$1") (pinfunction "1_P$1") (pintype "passive"))
      (node (ref "C59") (pin "P$1") (pinfunction "1_P$1") (pintype "passive"))
      (node (ref "C60") (pin "P$1") (pinfunction "1_P$1") (pintype "passive"))
      (node (ref "C61") (pin "P$2") (pinfunction "2_P$2") (pintype "passive"))
      (node (ref "FB2/2") (pin "1") (pinfunction "P$1_1") (pintype "bidirectional"))
      (node (ref "J11") (pin "2") (pinfunction "2_2") (pintype "passive"))
      (node (ref "J11") (pin "4") (pinfunction "4_4") (pintype "passive"))
      (node (ref "J9") (pin "4") (pinfunction "SUPPLY_VOLTAGE_4") (pintype "power_in"))
      (node (ref "L3") (pin "2") (pinfunction "P$2_2") (pintype "bidirectional"))
      (node (ref "R13") (pin "P$2") (pinfunction "2_P$2") (pintype "passive"))
      (node (ref "R18") (pin "P$2") (pinfunction "2_P$2") (pintype "passive"))
      (node (ref "R20") (pin "P$1") (pinfunction "1_P$1") (pintype "passive"))
      (node (ref "R21") (pin "P$1") (pinfunction "1_P$1") (pintype "passive"))
      (node (ref "R23") (pin "P$2") (pinfunction "2_P$2") (pintype "passive"))
      (node (ref "R24") (pin "P$2") (pinfunction "2_P$2") (pintype "passive"))
      (node (ref "R26") (pin "P$2") (pinfunction "2_P$2") (pintype "passive"))
      (node (ref "R27") (pin "P$2") (pinfunction "2_P$2") (pintype "passive"))
      (node (ref "R28") (pin "P$2") (pinfunction "2_P$2") (pintype "passive"))
      (node (ref "R29") (pin "P$2") (pinfunction "2_P$2") (pintype "passive"))
      (node (ref "U3") (pin "14") (pinfunction "VDDIO_14") (pintype "power_in"))
      (node (ref "U4") (pin "110") (pinfunction "VCC(IO)5_110") (pintype "bidirectional"))
      (node (ref "U4") (pin "123") (pinfunction "VCC(IO)6_123") (pintype "bidirectional"))
      (node (ref "U4") (pin "138") (pinfunction "VCC(IO)7_138") (pintype "bidirectional"))
      (node (ref "U4") (pin "149") (pinfunction "VCC(IO)8_149") (pintype "bidirectional"))
      (node (ref "U4") (pin "154") (pinfunction "VREFH_154") (pintype "bidirectional"))
      (node (ref "U4") (pin "155") (pinfunction "AVCC0_155") (pintype "bidirectional"))
      (node (ref "U4") (pin "158") (pinfunction "VREFH0_158") (pintype "bidirectional"))
      (node (ref "U4") (pin "171") (pinfunction "VCC(IO)9_171") (pintype "bidirectional"))
      (node (ref "U4") (pin "25") (pinfunction "VCC1_25") (pintype "bidirectional"))
      (node (ref "U4") (pin "26") (pinfunction "AVCC_SUBHS_26") (pintype "bidirectional"))
      (node (ref "U4") (pin "34") (pinfunction "VCC_USBHS_34") (pintype "bidirectional"))
      (node (ref "U4") (pin "48") (pinfunction "VCC_USB_48") (pintype "bidirectional"))
      (node (ref "U4") (pin "61") (pinfunction "VCC(IO)2_61") (pintype "bidirectional"))
      (node (ref "U4") (pin "84") (pinfunction "VCC(IO)3_84") (pintype "bidirectional"))
      (node (ref "U4") (pin "97") (pinfunction "VCC(IO)4_97") (pintype "bidirectional"))
    )
    (net (code "162") (name "VDD5") (class "Default")
      (node (ref "C5") (pin "P$1") (pinfunction "1_P$1") (pintype "passive"))
      (node (ref "C8") (pin "P$1") (pinfunction "1_P$1") (pintype "passive"))
      (node (ref "J1") (pin "P$3") (pinfunction "P$3_P$3") (pintype "bidirectional"))
      (node (ref "R1") (pin "P$2") (pinfunction "2_P$2") (pintype "passive"))
      (node (ref "R12") (pin "P$2") (pinfunction "2_P$2") (pintype "passive"))
      (node (ref "U2") (pin "4") (pinfunction "VIN_4") (pintype "input"))
    )
    (net (code "163") (name "VDDIN") (class "Default")
      (node (ref "J1") (pin "P$2") (pinfunction "P$2_P$2") (pintype "bidirectional"))
      (node (ref "L3") (pin "1") (pinfunction "P$1_1") (pintype "bidirectional"))
    )
    (net (code "164") (name "VDD_1.2") (class "Default")
      (node (ref "C45") (pin "P$1") (pinfunction "1_P$1") (pintype "passive"))
      (node (ref "C46") (pin "P$1") (pinfunction "1_P$1") (pintype "passive"))
      (node (ref "U3") (pin "1") (pinfunction "VDD_1.2_1") (pintype "power_in"))
    )
    (net (code "165") (name "XCIN") (class "Default")
      (node (ref "C50") (pin "P$1") (pinfunction "1_P$1") (pintype "passive"))
      (node (ref "U4") (pin "20") (pinfunction "XCIN_20") (pintype "bidirectional"))
      (node (ref "X3") (pin "P$1") (pinfunction "P$1_P$1") (pintype "bidirectional"))
    )
    (net (code "166") (name "XCOUT") (class "Default")
      (node (ref "C51") (pin "P$1") (pinfunction "1_P$1") (pintype "passive"))
      (node (ref "U4") (pin "21") (pinfunction "XCOUT_21") (pintype "bidirectional"))
      (node (ref "X3") (pin "P$2") (pinfunction "P$2_P$2") (pintype "bidirectional"))
    )
    (net (code "167") (name "XII") (class "Default")
      (node (ref "C42") (pin "P$1") (pinfunction "1_P$1") (pintype "passive"))
      (node (ref "U$3") (pin "1") (pinfunction "1_1") (pintype "bidirectional"))
      (node (ref "U3") (pin "8") (pinfunction "XI_8") (pintype "input"))
    )
    (net (code "168") (name "XOO") (class "Default")
      (node (ref "C41") (pin "P$1") (pinfunction "1_P$1") (pintype "passive"))
      (node (ref "U$3") (pin "3") (pinfunction "3_3") (pintype "bidirectional"))
      (node (ref "U3") (pin "7") (pinfunction "XO_7") (pintype "output"))
    )
    (net (code "169") (name "XTAL1") (class "Default")
      (node (ref "C52") (pin "P$1") (pinfunction "1_P$1") (pintype "passive"))
      (node (ref "U4") (pin "23") (pinfunction "P2_13/XTAL_23") (pintype "bidirectional"))
      (node (ref "X4") (pin "1") (pinfunction "1_1") (pintype "bidirectional"))
    )
    (net (code "170") (name "XTAL2") (class "Default")
      (node (ref "C53") (pin "P$1") (pinfunction "1_P$1") (pintype "passive"))
      (node (ref "U4") (pin "24") (pinfunction "P2_12/EXTAL_24") (pintype "bidirectional"))
      (node (ref "X4") (pin "3") (pinfunction "3_3") (pintype "bidirectional"))
    )
    (net (code "171") (name "unconnected-(U4-VBAT-Pad18)") (class "Default")
      (node (ref "U4") (pin "18") (pinfunction "VBAT_18") (pintype "bidirectional"))
    )
  )
)
